# EEZ_DIB_DCM220_r1B2.net
KiCad netlist of a schematic drawn in EAGLE
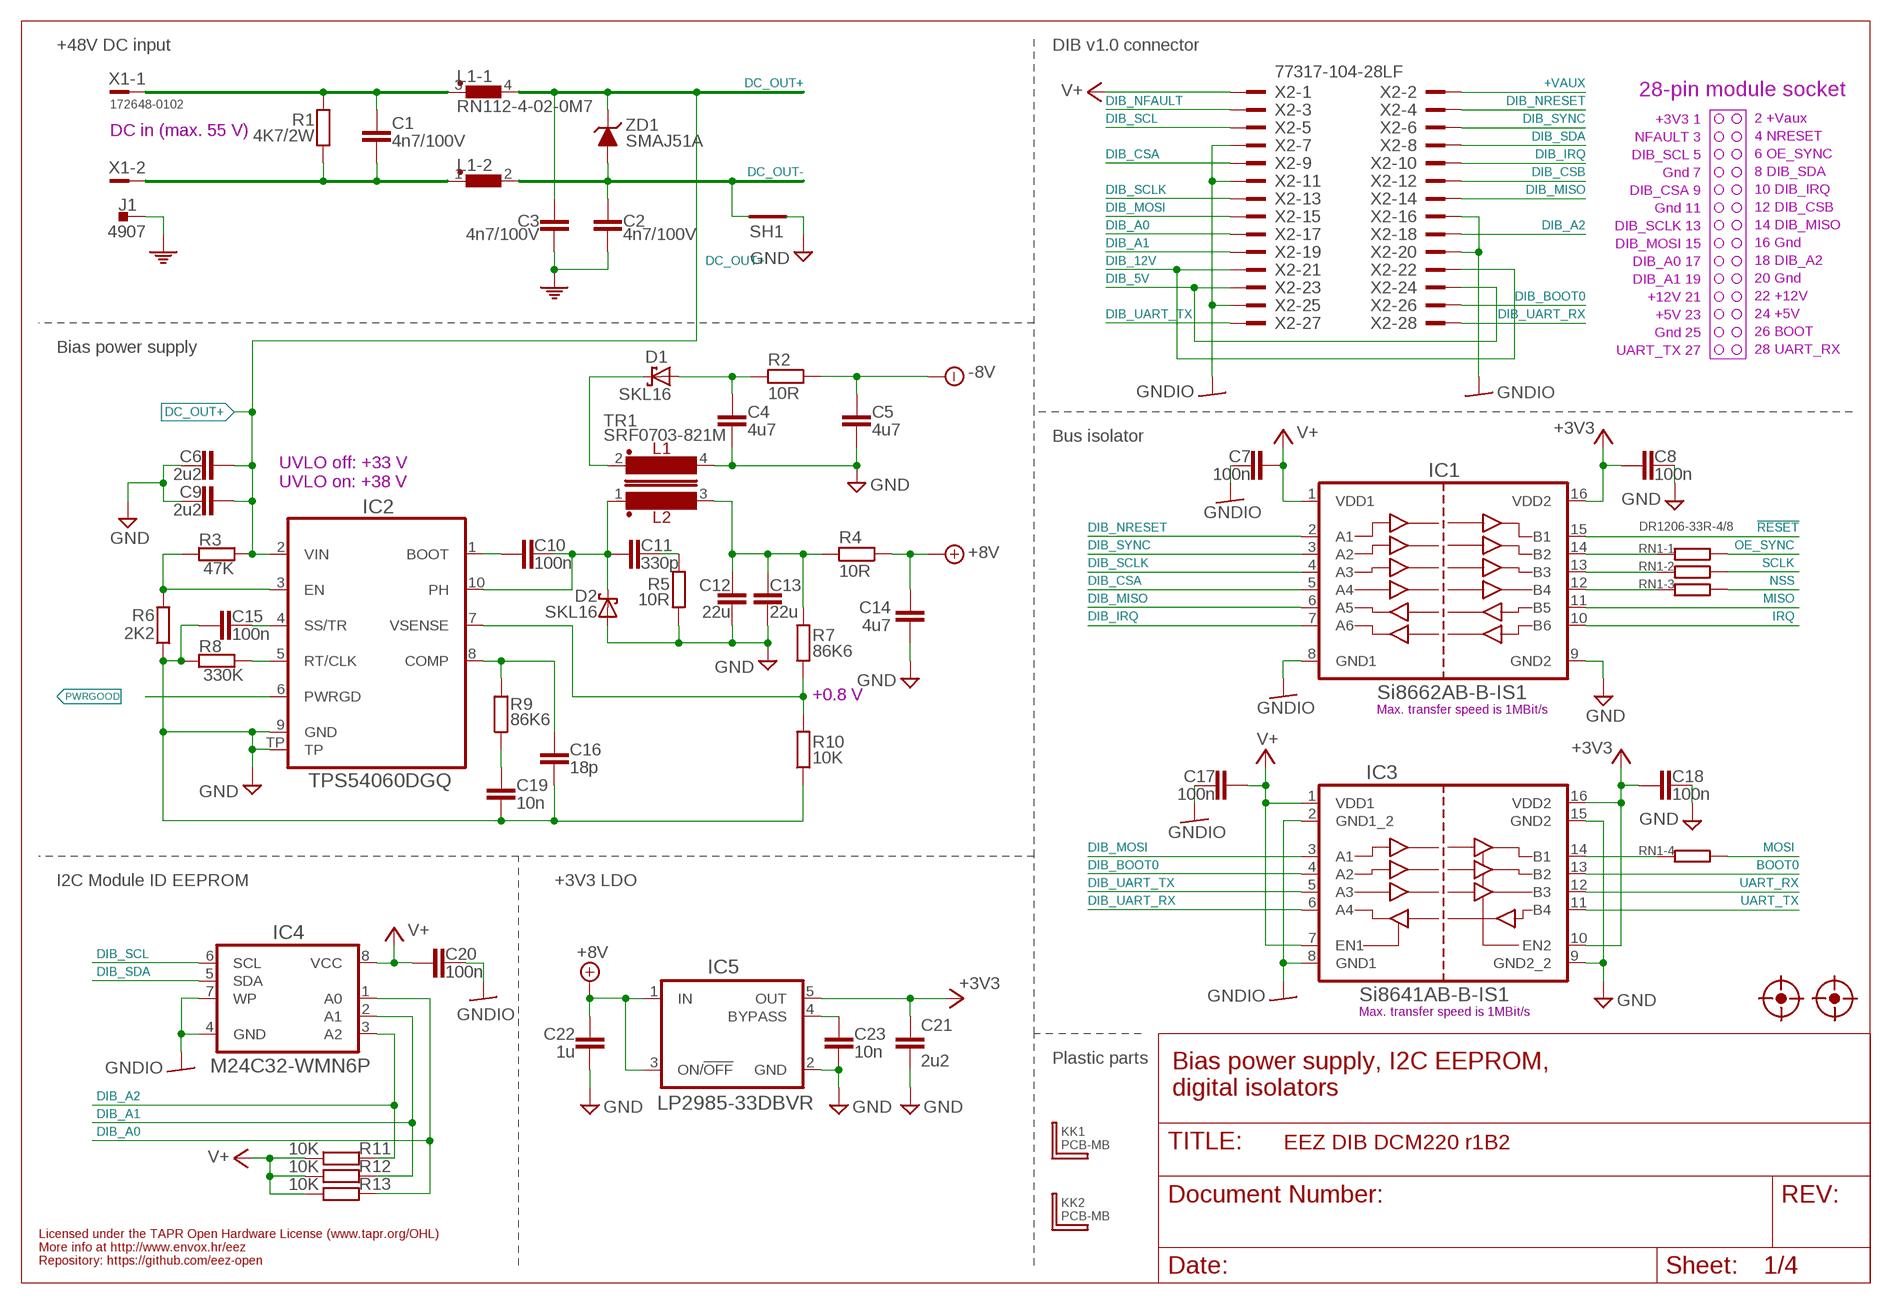
[diagram p0: schematic, sheet 1]
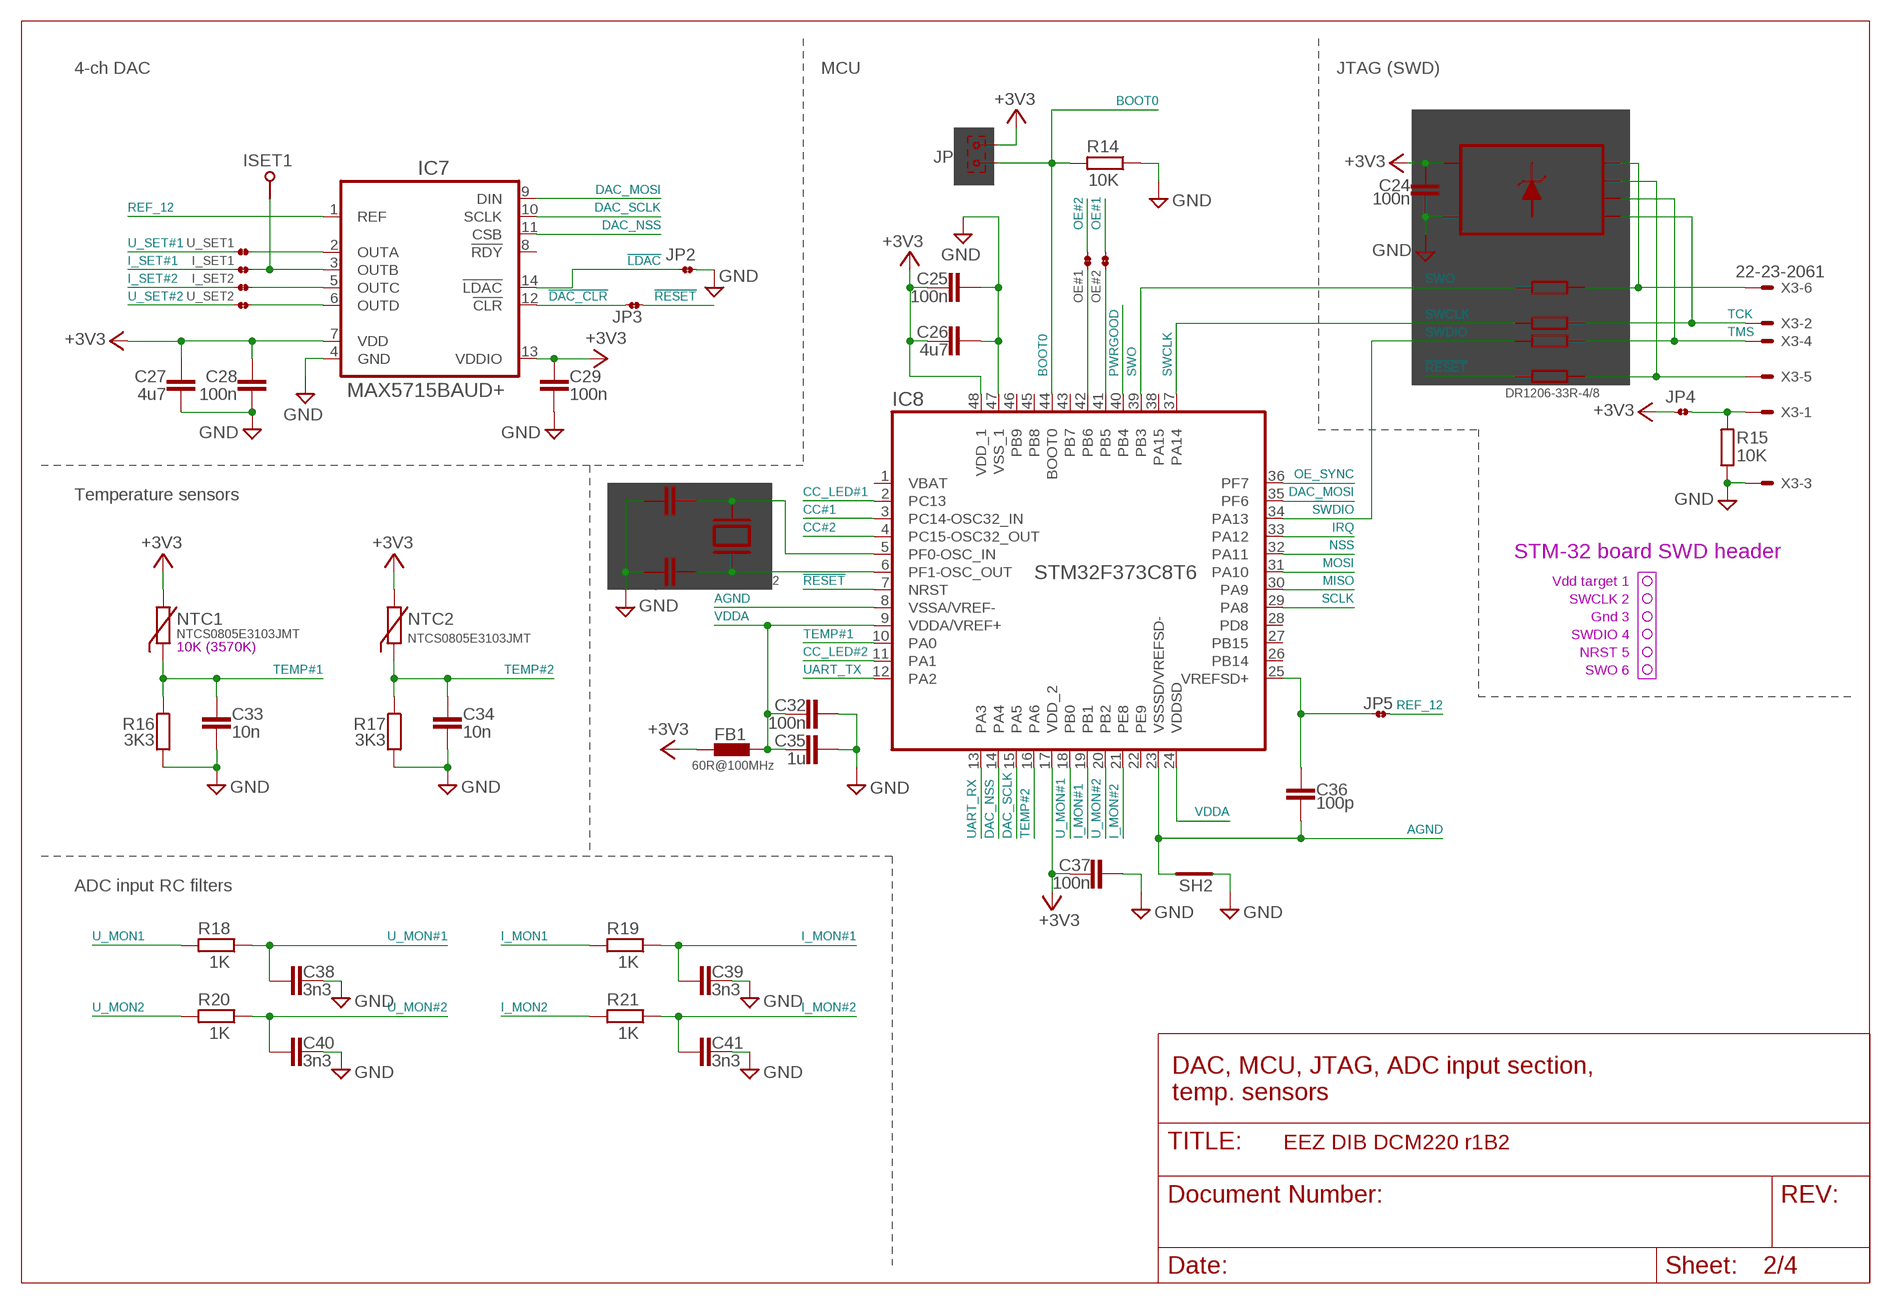
[diagram p1: schematic, sheet 2]
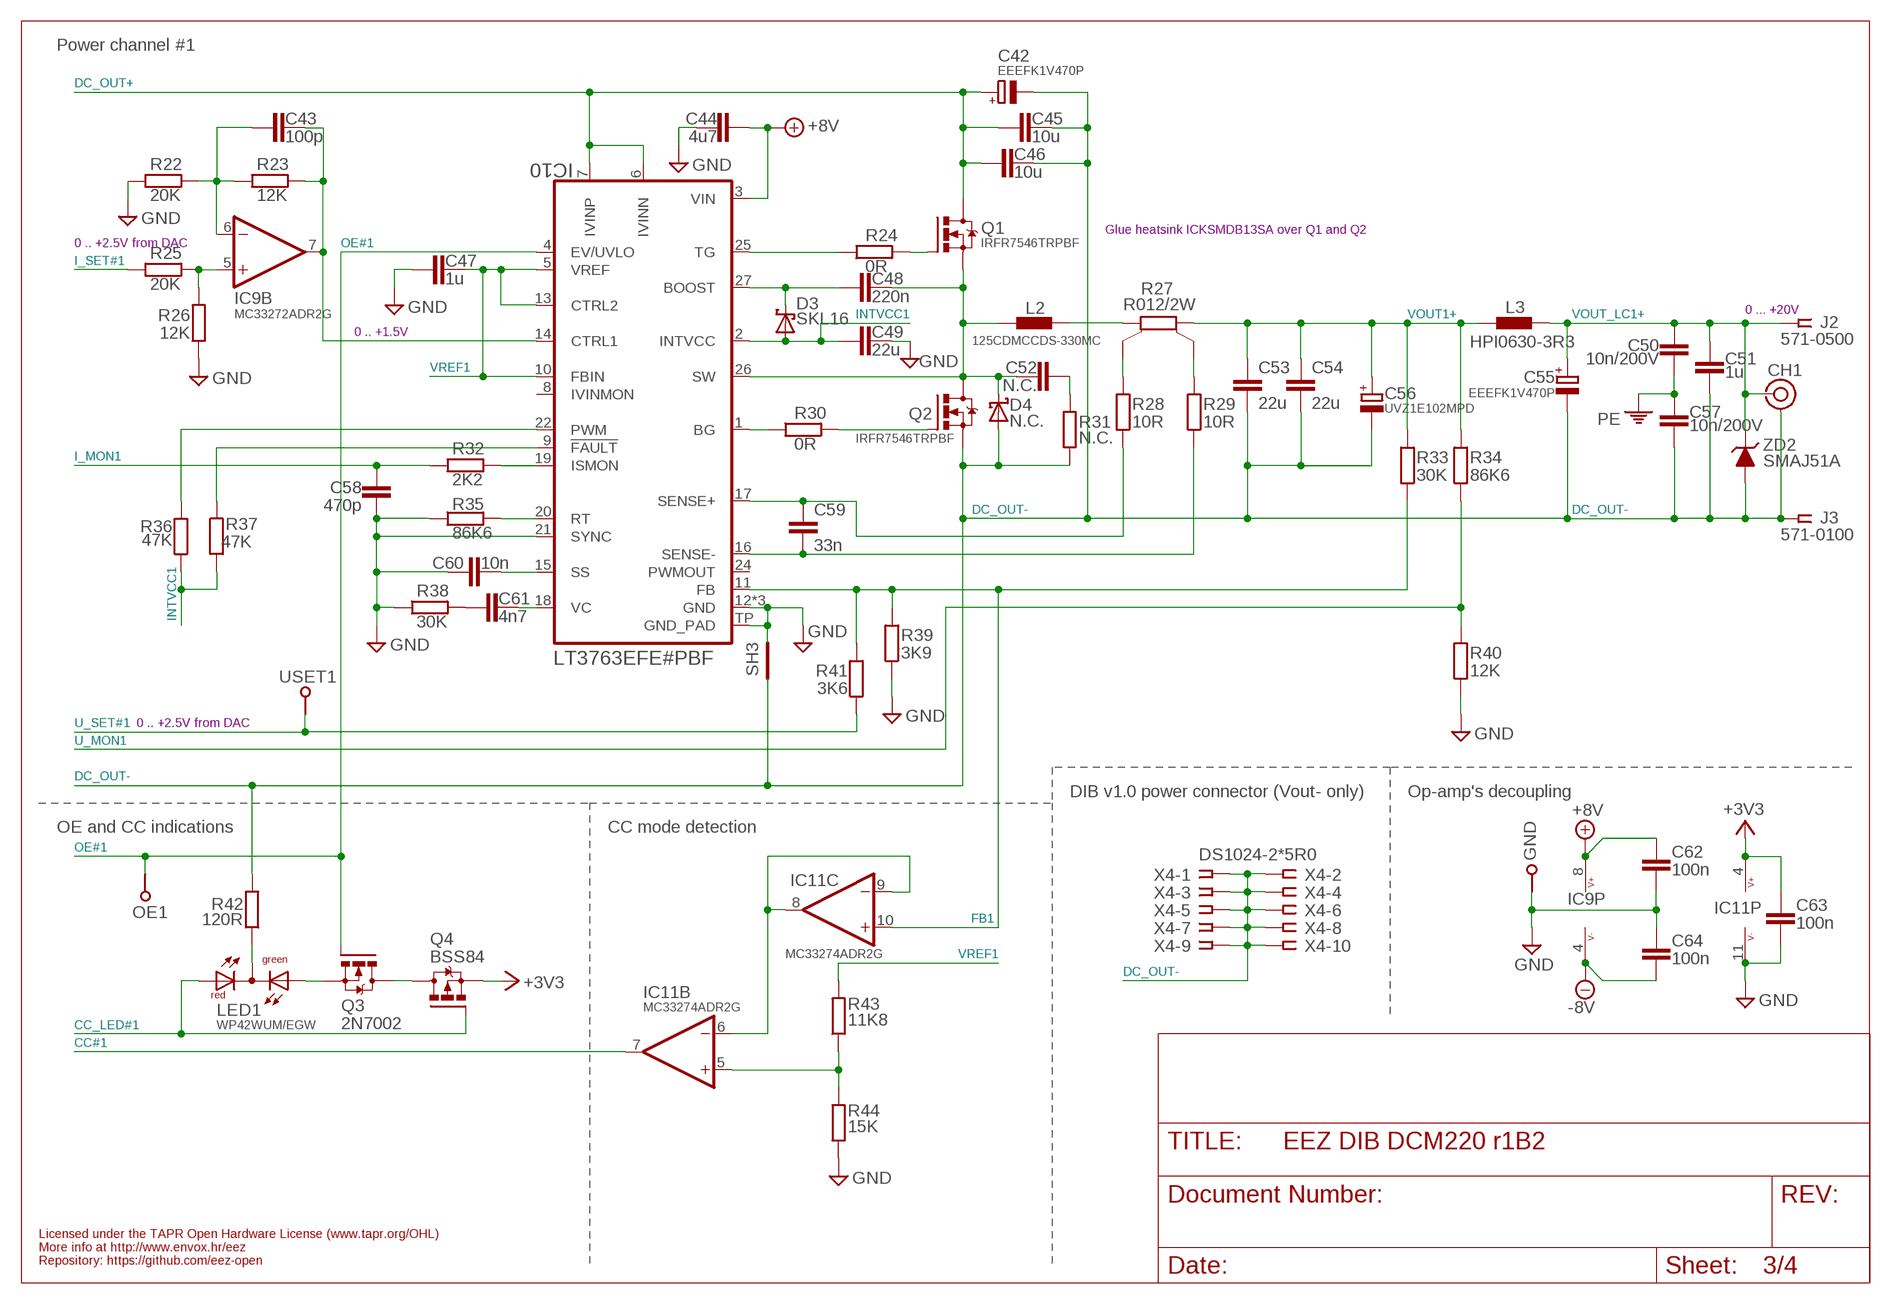
[diagram p2: schematic, sheet 3]
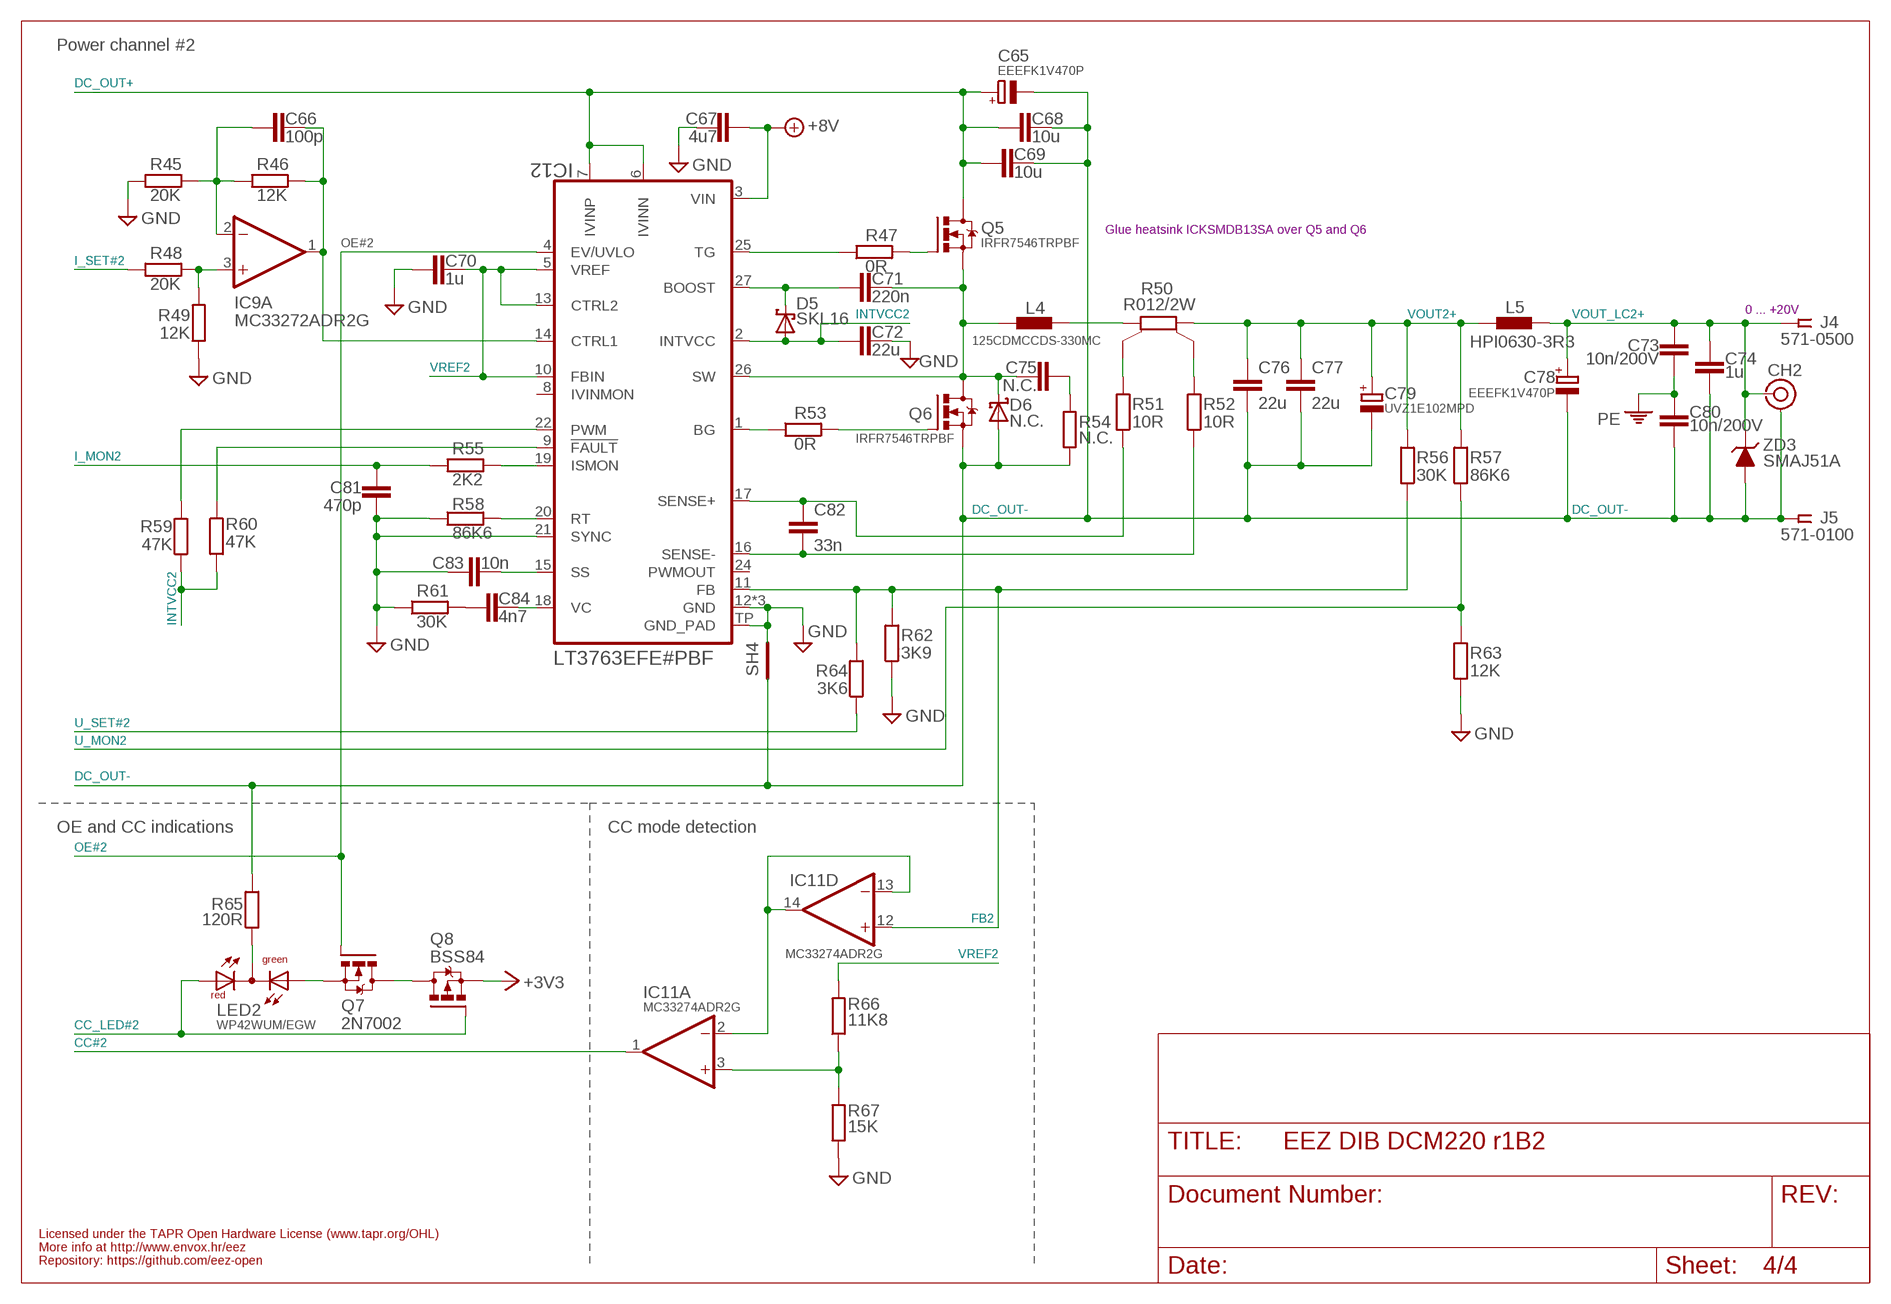
[diagram p3: schematic, sheet 4]

(export (version "E")
  (design (tool "Eeschema 10.0.6"))
  (components
    (comp (ref "C42")
      (value "EEEFK1V470P")
      (footprint "eagle-import:CAPAE830X1050N")
      (libsource (lib "eagle-import") (part "ECAPSMD8.3MM/HA0"))
    )
    (comp (ref "C43")
      (value "100p")
      (footprint "eagle-import:C0805")
      (libsource (lib "eagle-import") (part "C-EUC0805"))
    )
    (comp (ref "C44")
      (value "4u7")
      (footprint "eagle-import:C1206")
      (libsource (lib "eagle-import") (part "C-EUC1206"))
    )
    (comp (ref "C45")
      (value "10u")
      (footprint "eagle-import:C1210")
      (libsource (lib "eagle-import") (part "C-EUC1210"))
    )
    (comp (ref "C46")
      (value "10u")
      (footprint "eagle-import:C1210")
      (libsource (lib "eagle-import") (part "C-EUC1210"))
    )
    (comp (ref "C47")
      (value "1u")
      (footprint "eagle-import:C0805")
      (libsource (lib "eagle-import") (part "C-EUC0805"))
    )
    (comp (ref "C48")
      (value "220n")
      (footprint "eagle-import:C0805")
      (libsource (lib "eagle-import") (part "C-EUC0805"))
    )
    (comp (ref "C49")
      (value "22u")
      (footprint "eagle-import:C1210")
      (libsource (lib "eagle-import") (part "C-EUC1210"))
    )
    (comp (ref "C50")
      (value "10n/200V")
      (footprint "eagle-import:C1206")
      (libsource (lib "eagle-import") (part "C-EUC1206"))
    )
    (comp (ref "C51")
      (value "1u")
      (footprint "eagle-import:C0805")
      (libsource (lib "eagle-import") (part "C-EUC0805"))
    )
    (comp (ref "C52")
      (value "N.C.")
      (footprint "eagle-import:C0805")
      (libsource (lib "eagle-import") (part "C-EUC0805"))
    )
    (comp (ref "C53")
      (value "22u")
      (footprint "eagle-import:C1210")
      (libsource (lib "eagle-import") (part "C-EUC1210"))
    )
    (comp (ref "C54")
      (value "22u")
      (footprint "eagle-import:C1210")
      (libsource (lib "eagle-import") (part "C-EUC1210"))
    )
    (comp (ref "C55")
      (value "EEEFK1V470P")
      (footprint "eagle-import:CAPAE830X1050N")
      (libsource (lib "eagle-import") (part "ECAPSMD8.3MM/HA0"))
    )
    (comp (ref "C56")
      (value "UVZ1E102MPD")
      (footprint "eagle-import:ECAP5_10.5")
      (libsource (lib "eagle-import") (part "ECAP5G_10.5MM"))
    )
    (comp (ref "C57")
      (value "10n/200V")
      (footprint "eagle-import:C1206")
      (libsource (lib "eagle-import") (part "C-EUC1206"))
    )
    (comp (ref "C58")
      (value "470p")
      (footprint "eagle-import:C0805")
      (libsource (lib "eagle-import") (part "C-EUC0805"))
    )
    (comp (ref "C59")
      (value "33n")
      (footprint "eagle-import:C0805")
      (libsource (lib "eagle-import") (part "C-EUC0805"))
    )
    (comp (ref "C60")
      (value "10n")
      (footprint "eagle-import:C0805")
      (libsource (lib "eagle-import") (part "C-EUC0805"))
    )
    (comp (ref "C61")
      (value "4n7")
      (footprint "eagle-import:C0805")
      (libsource (lib "eagle-import") (part "C-EUC0805"))
    )
    (comp (ref "C62")
      (value "100n")
      (footprint "eagle-import:C0603")
      (libsource (lib "eagle-import") (part "C-EUC0603"))
    )
    (comp (ref "C63")
      (value "100n")
      (footprint "eagle-import:C0603")
      (libsource (lib "eagle-import") (part "C-EUC0603"))
    )
    (comp (ref "C64")
      (value "100n")
      (footprint "eagle-import:C0603")
      (libsource (lib "eagle-import") (part "C-EUC0603"))
    )
    (comp (ref "CH1")
      (value "TEST_POINT-2")
      (footprint "eagle-import:TP_1.1MM_2")
      (libsource (lib "eagle-import") (part "TEST_POINT-2"))
    )
    (comp (ref "D3")
      (value "SKL16")
      (footprint "eagle-import:SOD123")
      (libsource (lib "eagle-import") (part "SCHOTTKYSOD123"))
    )
    (comp (ref "D4")
      (value "N.C.")
      (footprint "eagle-import:SMA")
      (libsource (lib "eagle-import") (part "SCHOTTKYSMA_DO-214AC"))
    )
    (comp (ref "GND")
      (value "TEST-PIN_0.9MM")
      (footprint "eagle-import:TEST-PIN_0.9MM")
      (libsource (lib "eagle-import") (part "TEST-PIN_0.9MM"))
    )
    (comp (ref "IC9")
      (value "MC33272ADR2G")
      (footprint "eagle-import:SOIC127P600X173-8N")
      (libsource (lib "eagle-import") (part "TL072SOIC8"))
    )
    (comp (ref "IC10")
      (value "LT3763EFE#PBF")
      (footprint "eagle-import:LTC_05-08-1663-EB")
      (libsource (lib "eagle-import") (part "LT3763EFE#PBF"))
    )
    (comp (ref "IC11")
      (value "MC33274ADR2G")
      (footprint "eagle-import:SOIC127P600X175-14N")
      (fields (field (name "MPN") "TL074ACD"))
      (libsource (lib "eagle-import") (part "TL074SOIC14"))
    )
    (comp (ref "J2")
      (value "571-0500")
      (footprint "eagle-import:DELTRON_571")
      (libsource (lib "eagle-import") (part "571-0500"))
    )
    (comp (ref "J3")
      (value "571-0100")
      (footprint "eagle-import:DELTRON_571")
      (libsource (lib "eagle-import") (part "571-0100"))
    )
    (comp (ref "L2")
      (value "125CDMCCDS-330MC")
      (footprint "eagle-import:125CDMCC_DS")
      (libsource (lib "eagle-import") (part "125CDMCC/DS"))
    )
    (comp (ref "L3")
      (value "HPI0630-3R3")
      (footprint "eagle-import:COILCRAFT_HPI0630")
      (libsource (lib "eagle-import") (part "COILCRAFT_HPI0630"))
    )
    (comp (ref "LED1")
      (value "WP42WUM/EGW")
      (footprint "eagle-import:L-42WUM-1EGWT")
      (libsource (lib "eagle-import") (part "LED_L-42WUM/1EGWT"))
    )
    (comp (ref "OE1")
      (value "TEST-PIN_0.9MM")
      (footprint "eagle-import:TEST-PIN_0.9MM")
      (libsource (lib "eagle-import") (part "TEST-PIN_0.9MM"))
    )
    (comp (ref "Q1")
      (value "IRFR7546TRPBF")
      (footprint "eagle-import:TO229P990X239-3N")
      (libsource (lib "eagle-import") (part "N-MOSFETDPAK"))
    )
    (comp (ref "Q2")
      (value "IRFR7546TRPBF")
      (footprint "eagle-import:TO229P990X239-3N")
      (libsource (lib "eagle-import") (part "N-MOSFETDPAK"))
    )
    (comp (ref "Q3")
      (value "2N7002")
      (footprint "eagle-import:SOT103P240X110-3N")
      (fields (field (name "MPN") "2N7002-7-F"))
      (libsource (lib "eagle-import") (part "2N7002"))
    )
    (comp (ref "Q4")
      (value "BSS84")
      (footprint "eagle-import:SOT95P237X112-3N")
      (fields (field (name "MPN") "IRLML2246TRPBF"))
      (libsource (lib "eagle-import") (part "IRLML2246TRPBF"))
    )
    (comp (ref "R22")
      (value "20K")
      (footprint "eagle-import:R0805")
      (libsource (lib "eagle-import") (part "R-EU_R0805"))
    )
    (comp (ref "R23")
      (value "12K")
      (footprint "eagle-import:R0805")
      (libsource (lib "eagle-import") (part "R-EU_R0805"))
    )
    (comp (ref "R24")
      (value "0R")
      (footprint "eagle-import:R0805")
      (libsource (lib "eagle-import") (part "R-EU_R0805"))
    )
    (comp (ref "R25")
      (value "20K")
      (footprint "eagle-import:R0805")
      (libsource (lib "eagle-import") (part "R-EU_R0805"))
    )
    (comp (ref "R26")
      (value "12K")
      (footprint "eagle-import:R0805")
      (libsource (lib "eagle-import") (part "R-EU_R0805"))
    )
    (comp (ref "R27")
      (value "R012/2W")
      (footprint "eagle-import:R_2512-4WIRE")
      (libsource (lib "eagle-import") (part "R-EU_4WIRE2512"))
    )
    (comp (ref "R28")
      (value "10R")
      (footprint "eagle-import:R0805")
      (libsource (lib "eagle-import") (part "R-EU_R0805"))
    )
    (comp (ref "R29")
      (value "10R")
      (footprint "eagle-import:R0805")
      (libsource (lib "eagle-import") (part "R-EU_R0805"))
    )
    (comp (ref "R30")
      (value "0R")
      (footprint "eagle-import:R0805")
      (libsource (lib "eagle-import") (part "R-EU_R0805"))
    )
    (comp (ref "R31")
      (value "N.C.")
      (footprint "eagle-import:R1206")
      (libsource (lib "eagle-import") (part "R-EU_R1206"))
    )
    (comp (ref "R32")
      (value "2K2")
      (footprint "eagle-import:R0805")
      (libsource (lib "eagle-import") (part "R-EU_R0805"))
    )
    (comp (ref "R33")
      (value "30K")
      (footprint "eagle-import:R0805")
      (libsource (lib "eagle-import") (part "R-EU_R0805"))
    )
    (comp (ref "R34")
      (value "86K6")
      (footprint "eagle-import:R0805")
      (libsource (lib "eagle-import") (part "R-EU_R0805"))
    )
    (comp (ref "R35")
      (value "86K6")
      (footprint "eagle-import:R0805")
      (libsource (lib "eagle-import") (part "R-EU_R0805"))
    )
    (comp (ref "R36")
      (value "47K")
      (footprint "eagle-import:R0805")
      (libsource (lib "eagle-import") (part "R-EU_R0805"))
    )
    (comp (ref "R37")
      (value "47K")
      (footprint "eagle-import:R0805")
      (libsource (lib "eagle-import") (part "R-EU_R0805"))
    )
    (comp (ref "R38")
      (value "30K")
      (footprint "eagle-import:R0805")
      (libsource (lib "eagle-import") (part "R-EU_R0805"))
    )
    (comp (ref "R39")
      (value "3K9")
      (footprint "eagle-import:R0805")
      (libsource (lib "eagle-import") (part "R-EU_R0805"))
    )
    (comp (ref "R40")
      (value "12K")
      (footprint "eagle-import:R0805")
      (libsource (lib "eagle-import") (part "R-EU_R0805"))
    )
    (comp (ref "R41")
      (value "3K6")
      (footprint "eagle-import:R0805")
      (libsource (lib "eagle-import") (part "R-EU_R0805"))
    )
    (comp (ref "R42")
      (value "120R")
      (footprint "eagle-import:R0805")
      (libsource (lib "eagle-import") (part "R-EU_R0805"))
    )
    (comp (ref "R43")
      (value "11K8")
      (footprint "eagle-import:R0805")
      (libsource (lib "eagle-import") (part "R-EU_R0805"))
    )
    (comp (ref "R44")
      (value "15K")
      (footprint "eagle-import:R0805")
      (libsource (lib "eagle-import") (part "R-EU_R0805"))
    )
    (comp (ref "SH3")
      (value "SHORTNOHOLE")
      (footprint "eagle-import:SHORT_NOHOLE")
      (libsource (lib "eagle-import") (part "SHORTNOHOLE"))
    )
    (comp (ref "USET1")
      (value "TEST-PIN_0.9MM")
      (footprint "eagle-import:TEST-PIN_0.9MM")
      (libsource (lib "eagle-import") (part "TEST-PIN_0.9MM"))
    )
    (comp (ref "X4")
      (value "DS1024-2*5R0")
      (footprint "eagle-import:SSW-105-02-T-D-RA")
      (libsource (lib "eagle-import") (part "SSW-105-02-T-D-RA"))
    )
    (comp (ref "ZD2")
      (value "SMAJ51A")
      (footprint "eagle-import:DO214AA")
      (libsource (lib "eagle-import") (part "P6SMB68A"))
    )
    (comp (ref "C1")
      (value "4n7/100V")
      (footprint "eagle-import:C1206")
      (libsource (lib "eagle-import") (part "C-EUC1206"))
    )
    (comp (ref "C2")
      (value "4n7/100V")
      (footprint "eagle-import:C1206")
      (libsource (lib "eagle-import") (part "C-EUC1206"))
    )
    (comp (ref "C3")
      (value "4n7/100V")
      (footprint "eagle-import:C1206")
      (libsource (lib "eagle-import") (part "C-EUC1206"))
    )
    (comp (ref "C4")
      (value "4u7")
      (footprint "eagle-import:C1206")
      (libsource (lib "eagle-import") (part "C-EUC1206"))
    )
    (comp (ref "C5")
      (value "4u7")
      (footprint "eagle-import:C1206")
      (libsource (lib "eagle-import") (part "C-EUC1206"))
    )
    (comp (ref "C6")
      (value "2u2")
      (footprint "eagle-import:C1206")
      (libsource (lib "eagle-import") (part "C-EUC1206"))
    )
    (comp (ref "C7")
      (value "100n")
      (footprint "eagle-import:C0603")
      (libsource (lib "eagle-import") (part "C-EUC0603"))
    )
    (comp (ref "C8")
      (value "100n")
      (footprint "eagle-import:C0603")
      (libsource (lib "eagle-import") (part "C-EUC0603"))
    )
    (comp (ref "C9")
      (value "2u2")
      (footprint "eagle-import:C1206")
      (libsource (lib "eagle-import") (part "C-EUC1206"))
    )
    (comp (ref "C10")
      (value "100n")
      (footprint "eagle-import:C0603")
      (libsource (lib "eagle-import") (part "C-EUC0603"))
    )
    (comp (ref "C11")
      (value "330p")
      (footprint "eagle-import:C0805")
      (libsource (lib "eagle-import") (part "C-EUC0805"))
    )
    (comp (ref "C12")
      (value "22u")
      (footprint "eagle-import:C1206")
      (libsource (lib "eagle-import") (part "C-EUC1206"))
    )
    (comp (ref "C13")
      (value "22u")
      (footprint "eagle-import:C1206")
      (libsource (lib "eagle-import") (part "C-EUC1206"))
    )
    (comp (ref "C14")
      (value "4u7")
      (footprint "eagle-import:C1206")
      (libsource (lib "eagle-import") (part "C-EUC1206"))
    )
    (comp (ref "C15")
      (value "100n")
      (footprint "eagle-import:C0603")
      (libsource (lib "eagle-import") (part "C-EUC0603"))
    )
    (comp (ref "C16")
      (value "18p")
      (footprint "eagle-import:C0603")
      (libsource (lib "eagle-import") (part "C-EUC0603"))
    )
    (comp (ref "C17")
      (value "100n")
      (footprint "eagle-import:C0603")
      (libsource (lib "eagle-import") (part "C-EUC0603"))
    )
    (comp (ref "C18")
      (value "100n")
      (footprint "eagle-import:C0603")
      (libsource (lib "eagle-import") (part "C-EUC0603"))
    )
    (comp (ref "C19")
      (value "10n")
      (footprint "eagle-import:C0805")
      (libsource (lib "eagle-import") (part "C-EUC0805"))
    )
    (comp (ref "C20")
      (value "100n")
      (footprint "eagle-import:C0603")
      (libsource (lib "eagle-import") (part "C-EUC0603"))
    )
    (comp (ref "C21")
      (value "2u2")
      (footprint "eagle-import:C1206")
      (libsource (lib "eagle-import") (part "C-EUC1206"))
    )
    (comp (ref "C22")
      (value "1u")
      (footprint "eagle-import:C0805")
      (libsource (lib "eagle-import") (part "C-EUC0805"))
    )
    (comp (ref "C23")
      (value "10n")
      (footprint "eagle-import:C0805")
      (libsource (lib "eagle-import") (part "C-EUC0805"))
    )
    (comp (ref "D1")
      (value "SKL16")
      (footprint "eagle-import:SOD123")
      (libsource (lib "eagle-import") (part "SCHOTTKYSOD123"))
    )
    (comp (ref "D2")
      (value "SKL16")
      (footprint "eagle-import:SOD123")
      (libsource (lib "eagle-import") (part "SCHOTTKYSOD123"))
    )
    (comp (ref "FM1")
      (value "FIDUCIAL_2")
      (footprint "eagle-import:FIDUCIAL_DUAL")
      (libsource (lib "eagle-import") (part "FIDUCIAL_2"))
    )
    (comp (ref "FM2")
      (value "FIDUCIAL_2")
      (footprint "eagle-import:FIDUCIAL_DUAL")
      (libsource (lib "eagle-import") (part "FIDUCIAL_2"))
    )
    (comp (ref "IC1")
      (value "Si8662AB-B-IS1")
      (footprint "eagle-import:SOIC-16")
      (libsource (lib "eagle-import") (part "SI8662NSOIC-16"))
    )
    (comp (ref "IC2")
      (value "TPS54060DGQ")
      (footprint "eagle-import:SOP50P490X110-11N")
      (fields (field (name "MPN") "TPS54060ADGQ"))
      (libsource (lib "eagle-import") (part "TPS54060DGQ"))
    )
    (comp (ref "IC3")
      (value "Si8641AB-B-IS1")
      (footprint "eagle-import:SOIC-16")
      (libsource (lib "eagle-import") (part "SI8641NSOIC-16"))
    )
    (comp (ref "IC4")
      (value "M24C32-WMN6P")
      (footprint "eagle-import:SOIC127P600X173-8N")
      (libsource (lib "eagle-import") (part "AT24CXXSOIC8"))
    )
    (comp (ref "IC5")
      (value "LP2985-33DBVR")
      (footprint "eagle-import:SOT95P270X145-5N")
      (libsource (lib "eagle-import") (part "LP2985"))
    )
    (comp (ref "J1")
      (value "4907")
      (footprint "eagle-import:PCB_TAB-4907")
      (libsource (lib "eagle-import") (part "PCB_TAB-4907"))
    )
    (comp (ref "KK1")
      (value "PCB-MB")
      (footprint "eagle-import:PCB-MB")
      (libsource (lib "eagle-import") (part "PCB-MB"))
    )
    (comp (ref "KK2")
      (value "PCB-MB")
      (footprint "eagle-import:PCB-MB")
      (libsource (lib "eagle-import") (part "PCB-MB"))
    )
    (comp (ref "L1")
      (value "RN112-4-02-0M7")
      (footprint "eagle-import:RN112")
      (libsource (lib "eagle-import") (part "RN112"))
    )
    (comp (ref "R1")
      (value "4K7/2W")
      (footprint "eagle-import:R2512")
      (libsource (lib "eagle-import") (part "R-EU_R2512"))
    )
    (comp (ref "R2")
      (value "10R")
      (footprint "eagle-import:R0805")
      (libsource (lib "eagle-import") (part "R-EU_R0805"))
    )
    (comp (ref "R3")
      (value "47K")
      (footprint "eagle-import:R0805")
      (libsource (lib "eagle-import") (part "R-EU_R0805"))
    )
    (comp (ref "R4")
      (value "10R")
      (footprint "eagle-import:R0805")
      (libsource (lib "eagle-import") (part "R-EU_R0805"))
    )
    (comp (ref "R5")
      (value "10R")
      (footprint "eagle-import:R0805")
      (libsource (lib "eagle-import") (part "R-EU_R0805"))
    )
    (comp (ref "R6")
      (value "2K2")
      (footprint "eagle-import:R0805")
      (libsource (lib "eagle-import") (part "R-EU_R0805"))
    )
    (comp (ref "R7")
      (value "86K6")
      (footprint "eagle-import:R0805")
      (libsource (lib "eagle-import") (part "R-EU_R0805"))
    )
    (comp (ref "R8")
      (value "330K")
      (footprint "eagle-import:R0805")
      (libsource (lib "eagle-import") (part "R-EU_R0805"))
    )
    (comp (ref "R9")
      (value "86K6")
      (footprint "eagle-import:R0805")
      (libsource (lib "eagle-import") (part "R-EU_R0805"))
    )
    (comp (ref "R10")
      (value "10K")
      (footprint "eagle-import:R0805")
      (libsource (lib "eagle-import") (part "R-EU_R0805"))
    )
    (comp (ref "R11")
      (value "10K")
      (footprint "eagle-import:R0805")
      (libsource (lib "eagle-import") (part "R-EU_R0805"))
    )
    (comp (ref "R12")
      (value "10K")
      (footprint "eagle-import:R0805")
      (libsource (lib "eagle-import") (part "R-EU_R0805"))
    )
    (comp (ref "R13")
      (value "10K")
      (footprint "eagle-import:R0805")
      (libsource (lib "eagle-import") (part "R-EU_R0805"))
    )
    (comp (ref "RN1")
      (value "DR1206-33R-4/8")
      (footprint "eagle-import:CAY16")
      (libsource (lib "eagle-import") (part "R_ARRAY4"))
    )
    (comp (ref "SH1")
      (value "SHORTNOHOLE")
      (footprint "eagle-import:SHORT_NOHOLE")
      (libsource (lib "eagle-import") (part "SHORTNOHOLE"))
    )
    (comp (ref "TR1")
      (value "SRF0703-821M")
      (footprint "eagle-import:SRF0703")
      (libsource (lib "eagle-import") (part "BOURNS_SRF0703INV"))
    )
    (comp (ref "X1")
      (value "172648-0102")
      (footprint "eagle-import:MINIFIT_39301020")
      (libsource (lib "eagle-import") (part "MINIFIT_39301020"))
    )
    (comp (ref "X2")
      (value "77317-104-28LF")
      (footprint "eagle-import:77317-104-28LF")
      (libsource (lib "eagle-import") (part "77317-104-28LF"))
    )
    (comp (ref "ZD1")
      (value "SMAJ51A")
      (footprint "eagle-import:DO214AA")
      (libsource (lib "eagle-import") (part "P6SMB68A"))
    )
    (comp (ref "C65")
      (value "EEEFK1V470P")
      (footprint "eagle-import:CAPAE830X1050N")
      (libsource (lib "eagle-import") (part "ECAPSMD8.3MM/HA0"))
    )
    (comp (ref "C66")
      (value "100p")
      (footprint "eagle-import:C0805")
      (libsource (lib "eagle-import") (part "C-EUC0805"))
    )
    (comp (ref "C67")
      (value "4u7")
      (footprint "eagle-import:C1206")
      (libsource (lib "eagle-import") (part "C-EUC1206"))
    )
    (comp (ref "C68")
      (value "10u")
      (footprint "eagle-import:C1210")
      (libsource (lib "eagle-import") (part "C-EUC1210"))
    )
    (comp (ref "C69")
      (value "10u")
      (footprint "eagle-import:C1210")
      (libsource (lib "eagle-import") (part "C-EUC1210"))
    )
    (comp (ref "C70")
      (value "1u")
      (footprint "eagle-import:C0805")
      (libsource (lib "eagle-import") (part "C-EUC0805"))
    )
    (comp (ref "C71")
      (value "220n")
      (footprint "eagle-import:C0805")
      (libsource (lib "eagle-import") (part "C-EUC0805"))
    )
    (comp (ref "C72")
      (value "22u")
      (footprint "eagle-import:C1210")
      (libsource (lib "eagle-import") (part "C-EUC1210"))
    )
    (comp (ref "C73")
      (value "10n/200V")
      (footprint "eagle-import:C1206")
      (libsource (lib "eagle-import") (part "C-EUC1206"))
    )
    (comp (ref "C74")
      (value "1u")
      (footprint "eagle-import:C0805")
      (libsource (lib "eagle-import") (part "C-EUC0805"))
    )
    (comp (ref "C75")
      (value "N.C.")
      (footprint "eagle-import:C0805")
      (libsource (lib "eagle-import") (part "C-EUC0805"))
    )
    (comp (ref "C76")
      (value "22u")
      (footprint "eagle-import:C1210")
      (libsource (lib "eagle-import") (part "C-EUC1210"))
    )
    (comp (ref "C77")
      (value "22u")
      (footprint "eagle-import:C1210")
      (libsource (lib "eagle-import") (part "C-EUC1210"))
    )
    (comp (ref "C78")
      (value "EEEFK1V470P")
      (footprint "eagle-import:CAPAE830X1050N")
      (libsource (lib "eagle-import") (part "ECAPSMD8.3MM/HA0"))
    )
    (comp (ref "C79")
      (value "UVZ1E102MPD")
      (footprint "eagle-import:ECAP5_10.5")
      (libsource (lib "eagle-import") (part "ECAP5G_10.5MM"))
    )
    (comp (ref "C80")
      (value "10n/200V")
      (footprint "eagle-import:C1206")
      (libsource (lib "eagle-import") (part "C-EUC1206"))
    )
    (comp (ref "C81")
      (value "470p")
      (footprint "eagle-import:C0805")
      (libsource (lib "eagle-import") (part "C-EUC0805"))
    )
    (comp (ref "C82")
      (value "33n")
      (footprint "eagle-import:C0805")
      (libsource (lib "eagle-import") (part "C-EUC0805"))
    )
    (comp (ref "C83")
      (value "10n")
      (footprint "eagle-import:C0805")
      (libsource (lib "eagle-import") (part "C-EUC0805"))
    )
    (comp (ref "C84")
      (value "4n7")
      (footprint "eagle-import:C0805")
      (libsource (lib "eagle-import") (part "C-EUC0805"))
    )
    (comp (ref "CH2")
      (value "TEST_POINT-2")
      (footprint "eagle-import:TP_1.1MM_2")
      (libsource (lib "eagle-import") (part "TEST_POINT-2"))
    )
    (comp (ref "D5")
      (value "SKL16")
      (footprint "eagle-import:SOD123")
      (libsource (lib "eagle-import") (part "SCHOTTKYSOD123"))
    )
    (comp (ref "D6")
      (value "N.C.")
      (footprint "eagle-import:SMA")
      (libsource (lib "eagle-import") (part "SCHOTTKYSMA_DO-214AC"))
    )
    (comp (ref "IC12")
      (value "LT3763EFE#PBF")
      (footprint "eagle-import:LTC_05-08-1663-EB")
      (libsource (lib "eagle-import") (part "LT3763EFE#PBF"))
    )
    (comp (ref "J4")
      (value "571-0500")
      (footprint "eagle-import:DELTRON_571")
      (libsource (lib "eagle-import") (part "571-0500"))
    )
    (comp (ref "J5")
      (value "571-0100")
      (footprint "eagle-import:DELTRON_571")
      (libsource (lib "eagle-import") (part "571-0100"))
    )
    (comp (ref "L4")
      (value "125CDMCCDS-330MC")
      (footprint "eagle-import:125CDMCC_DS")
      (libsource (lib "eagle-import") (part "125CDMCC/DS"))
    )
    (comp (ref "L5")
      (value "HPI0630-3R3")
      (footprint "eagle-import:COILCRAFT_HPI0630")
      (libsource (lib "eagle-import") (part "COILCRAFT_HPI0630"))
    )
    (comp (ref "LED2")
      (value "WP42WUM/EGW")
      (footprint "eagle-import:L-42WUM-1EGWT")
      (libsource (lib "eagle-import") (part "LED_L-42WUM/1EGWT"))
    )
    (comp (ref "Q5")
      (value "IRFR7546TRPBF")
      (footprint "eagle-import:TO229P990X239-3N")
      (libsource (lib "eagle-import") (part "N-MOSFETDPAK"))
    )
    (comp (ref "Q6")
      (value "IRFR7546TRPBF")
      (footprint "eagle-import:TO229P990X239-3N")
      (libsource (lib "eagle-import") (part "N-MOSFETDPAK"))
    )
    (comp (ref "Q7")
      (value "2N7002")
      (footprint "eagle-import:SOT103P240X110-3N")
      (fields (field (name "MPN") "2N7002-7-F"))
      (libsource (lib "eagle-import") (part "2N7002"))
    )
    (comp (ref "Q8")
      (value "BSS84")
      (footprint "eagle-import:SOT95P237X112-3N")
      (fields (field (name "MPN") "IRLML2246TRPBF"))
      (libsource (lib "eagle-import") (part "IRLML2246TRPBF"))
    )
    (comp (ref "R45")
      (value "20K")
      (footprint "eagle-import:R0805")
      (libsource (lib "eagle-import") (part "R-EU_R0805"))
    )
    (comp (ref "R46")
      (value "12K")
      (footprint "eagle-import:R0805")
      (libsource (lib "eagle-import") (part "R-EU_R0805"))
    )
    (comp (ref "R47")
      (value "0R")
      (footprint "eagle-import:R0805")
      (libsource (lib "eagle-import") (part "R-EU_R0805"))
    )
    (comp (ref "R48")
      (value "20K")
      (footprint "eagle-import:R0805")
      (libsource (lib "eagle-import") (part "R-EU_R0805"))
    )
    (comp (ref "R49")
      (value "12K")
      (footprint "eagle-import:R0805")
      (libsource (lib "eagle-import") (part "R-EU_R0805"))
    )
    (comp (ref "R50")
      (value "R012/2W")
      (footprint "eagle-import:R_2512-4WIRE")
      (libsource (lib "eagle-import") (part "R-EU_4WIRE2512"))
    )
    (comp (ref "R51")
      (value "10R")
      (footprint "eagle-import:R0805")
      (libsource (lib "eagle-import") (part "R-EU_R0805"))
    )
    (comp (ref "R52")
      (value "10R")
      (footprint "eagle-import:R0805")
      (libsource (lib "eagle-import") (part "R-EU_R0805"))
    )
    (comp (ref "R53")
      (value "0R")
      (footprint "eagle-import:R0805")
      (libsource (lib "eagle-import") (part "R-EU_R0805"))
    )
    (comp (ref "R54")
      (value "N.C.")
      (footprint "eagle-import:R1206")
      (libsource (lib "eagle-import") (part "R-EU_R1206"))
    )
    (comp (ref "R55")
      (value "2K2")
      (footprint "eagle-import:R0805")
      (libsource (lib "eagle-import") (part "R-EU_R0805"))
    )
    (comp (ref "R56")
      (value "30K")
      (footprint "eagle-import:R0805")
      (libsource (lib "eagle-import") (part "R-EU_R0805"))
    )
    (comp (ref "R57")
      (value "86K6")
      (footprint "eagle-import:R0805")
      (libsource (lib "eagle-import") (part "R-EU_R0805"))
    )
    (comp (ref "R58")
      (value "86K6")
      (footprint "eagle-import:R0805")
      (libsource (lib "eagle-import") (part "R-EU_R0805"))
    )
    (comp (ref "R59")
      (value "47K")
      (footprint "eagle-import:R0805")
      (libsource (lib "eagle-import") (part "R-EU_R0805"))
    )
    (comp (ref "R60")
      (value "47K")
      (footprint "eagle-import:R0805")
      (libsource (lib "eagle-import") (part "R-EU_R0805"))
    )
    (comp (ref "R61")
      (value "30K")
      (footprint "eagle-import:R0805")
      (libsource (lib "eagle-import") (part "R-EU_R0805"))
    )
    (comp (ref "R62")
      (value "3K9")
      (footprint "eagle-import:R0805")
      (libsource (lib "eagle-import") (part "R-EU_R0805"))
    )
    (comp (ref "R63")
      (value "12K")
      (footprint "eagle-import:R0805")
      (libsource (lib "eagle-import") (part "R-EU_R0805"))
    )
    (comp (ref "R64")
      (value "3K6")
      (footprint "eagle-import:R0805")
      (libsource (lib "eagle-import") (part "R-EU_R0805"))
    )
    (comp (ref "R65")
      (value "120R")
      (footprint "eagle-import:R0805")
      (libsource (lib "eagle-import") (part "R-EU_R0805"))
    )
    (comp (ref "R66")
      (value "11K8")
      (footprint "eagle-import:R0805")
      (libsource (lib "eagle-import") (part "R-EU_R0805"))
    )
    (comp (ref "R67")
      (value "15K")
      (footprint "eagle-import:R0805")
      (libsource (lib "eagle-import") (part "R-EU_R0805"))
    )
    (comp (ref "SH4")
      (value "SHORTNOHOLE")
      (footprint "eagle-import:SHORT_NOHOLE")
      (libsource (lib "eagle-import") (part "SHORTNOHOLE"))
    )
    (comp (ref "ZD3")
      (value "SMAJ51A")
      (footprint "eagle-import:DO214AA")
      (libsource (lib "eagle-import") (part "P6SMB68A"))
    )
    (comp (ref "C24")
      (value "100n")
      (footprint "eagle-import:C0603")
      (libsource (lib "eagle-import") (part "C-EUC0603"))
    )
    (comp (ref "C25")
      (value "100n")
      (footprint "eagle-import:C0603")
      (libsource (lib "eagle-import") (part "C-EUC0603"))
    )
    (comp (ref "C26")
      (value "4u7")
      (footprint "eagle-import:C1206")
      (libsource (lib "eagle-import") (part "C-EUC1206"))
    )
    (comp (ref "C27")
      (value "4u7")
      (footprint "eagle-import:C1206")
      (libsource (lib "eagle-import") (part "C-EUC1206"))
    )
    (comp (ref "C28")
      (value "100n")
      (footprint "eagle-import:C0603")
      (libsource (lib "eagle-import") (part "C-EUC0603"))
    )
    (comp (ref "C29")
      (value "100n")
      (footprint "eagle-import:C0603")
      (libsource (lib "eagle-import") (part "C-EUC0603"))
    )
    (comp (ref "C30")
      (value "18p")
      (footprint "eagle-import:C0603")
      (libsource (lib "eagle-import") (part "C-EUC0603"))
    )
    (comp (ref "C31")
      (value "18p")
      (footprint "eagle-import:C0603")
      (libsource (lib "eagle-import") (part "C-EUC0603"))
    )
    (comp (ref "C32")
      (value "100n")
      (footprint "eagle-import:C0603")
      (libsource (lib "eagle-import") (part "C-EUC0603"))
    )
    (comp (ref "C33")
      (value "10n")
      (footprint "eagle-import:C0805")
      (libsource (lib "eagle-import") (part "C-EUC0805"))
    )
    (comp (ref "C34")
      (value "10n")
      (footprint "eagle-import:C0805")
      (libsource (lib "eagle-import") (part "C-EUC0805"))
    )
    (comp (ref "C35")
      (value "1u")
      (footprint "eagle-import:C0805")
      (libsource (lib "eagle-import") (part "C-EUC0805"))
    )
    (comp (ref "C36")
      (value "100p")
      (footprint "eagle-import:C0805")
      (libsource (lib "eagle-import") (part "C-EUC0805"))
    )
    (comp (ref "C37")
      (value "100n")
      (footprint "eagle-import:C0603")
      (libsource (lib "eagle-import") (part "C-EUC0603"))
    )
    (comp (ref "C38")
      (value "3n3")
      (footprint "eagle-import:C0805")
      (libsource (lib "eagle-import") (part "C-EUC0805"))
    )
    (comp (ref "C39")
      (value "3n3")
      (footprint "eagle-import:C0805")
      (libsource (lib "eagle-import") (part "C-EUC0805"))
    )
    (comp (ref "C40")
      (value "3n3")
      (footprint "eagle-import:C0805")
      (libsource (lib "eagle-import") (part "C-EUC0805"))
    )
    (comp (ref "C41")
      (value "3n3")
      (footprint "eagle-import:C0805")
      (libsource (lib "eagle-import") (part "C-EUC0805"))
    )
    (comp (ref "FB1")
      (value "60R@100MHz")
      (footprint "eagle-import:BEAD0603")
      (libsource (lib "eagle-import") (part "FERRITE_BEAD0603"))
    )
    (comp (ref "IC6")
      (value "TPD4E001DRLR")
      (footprint "eagle-import:DRL6")
      (libsource (lib "eagle-import") (part "TPD4E001-DRL"))
    )
    (comp (ref "IC7")
      (value "MAX5715BAUD+")
      (footprint "eagle-import:21-0066J_14")
      (libsource (lib "eagle-import") (part "MAX5715BAUD+"))
    )
    (comp (ref "IC8")
      (value "STM32F373C8T6")
      (footprint "eagle-import:LQFP-48")
      (libsource (lib "eagle-import") (part "STM32F373C8T6"))
    )
    (comp (ref "ISET1")
      (value "TEST-PIN_0.9MM")
      (footprint "eagle-import:TEST-PIN_0.9MM")
      (libsource (lib "eagle-import") (part "TEST-PIN_0.9MM"))
    )
    (comp (ref "I_SET1")
      (value "JP2-NOCUT")
      (footprint "eagle-import:JP2-NOCUT")
      (libsource (lib "eagle-import") (part "JP2-NOCUT"))
    )
    (comp (ref "I_SET2")
      (value "JP2-NOCUT")
      (footprint "eagle-import:JP2-NOCUT")
      (libsource (lib "eagle-import") (part "JP2-NOCUT"))
    )
    (comp (ref "JP1")
      (value "JUMPER-2PIN-2MM")
      (footprint "eagle-import:2MM-2")
      (libsource (lib "eagle-import") (part "JUMPER-2PIN-2MM"))
    )
    (comp (ref "JP2")
      (value "JP2-NOCUT")
      (footprint "eagle-import:JP2-NOCUT")
      (libsource (lib "eagle-import") (part "JP2-NOCUT"))
    )
    (comp (ref "JP3")
      (value "JP2-NOCUT")
      (footprint "eagle-import:JP2-NOCUT")
      (libsource (lib "eagle-import") (part "JP2-NOCUT"))
    )
    (comp (ref "JP4")
      (value "JP2-CUT")
      (footprint "eagle-import:JP2-CUT")
      (libsource (lib "eagle-import") (part "JP2-CUT"))
    )
    (comp (ref "JP5")
      (value "JP2-NOCUT")
      (footprint "eagle-import:JP2-NOCUT")
      (libsource (lib "eagle-import") (part "JP2-NOCUT"))
    )
    (comp (ref "NTC1")
      (value "NTCS0805E3103JMT")
      (footprint "eagle-import:R_0805")
      (libsource (lib "eagle-import") (part "NTCR_0805"))
    )
    (comp (ref "NTC2")
      (value "NTCS0805E3103JMT")
      (footprint "eagle-import:R_0805")
      (libsource (lib "eagle-import") (part "NTCR_0805"))
    )
    (comp (ref "OE#1")
      (value "JP2-NOCUT")
      (footprint "eagle-import:JP2-NOCUT")
      (libsource (lib "eagle-import") (part "JP2-NOCUT"))
    )
    (comp (ref "OE#2")
      (value "JP2-NOCUT")
      (footprint "eagle-import:JP2-NOCUT")
      (libsource (lib "eagle-import") (part "JP2-NOCUT"))
    )
    (comp (ref "R14")
      (value "10K")
      (footprint "eagle-import:R0805")
      (libsource (lib "eagle-import") (part "R-EU_R0805"))
    )
    (comp (ref "R15")
      (value "10K")
      (footprint "eagle-import:R0805")
      (libsource (lib "eagle-import") (part "R-EU_R0805"))
    )
    (comp (ref "R16")
      (value "3K3")
      (footprint "eagle-import:R0805")
      (libsource (lib "eagle-import") (part "R-EU_R0805"))
    )
    (comp (ref "R17")
      (value "3K3")
      (footprint "eagle-import:R0805")
      (libsource (lib "eagle-import") (part "R-EU_R0805"))
    )
    (comp (ref "R18")
      (value "1K")
      (footprint "eagle-import:R0805")
      (libsource (lib "eagle-import") (part "R-EU_R0805"))
    )
    (comp (ref "R19")
      (value "1K")
      (footprint "eagle-import:R0805")
      (libsource (lib "eagle-import") (part "R-EU_R0805"))
    )
    (comp (ref "R20")
      (value "1K")
      (footprint "eagle-import:R0805")
      (libsource (lib "eagle-import") (part "R-EU_R0805"))
    )
    (comp (ref "R21")
      (value "1K")
      (footprint "eagle-import:R0805")
      (libsource (lib "eagle-import") (part "R-EU_R0805"))
    )
    (comp (ref "RN2")
      (value "DR1206-33R-4/8")
      (footprint "eagle-import:CAY16")
      (libsource (lib "eagle-import") (part "R_ARRAY4"))
    )
    (comp (ref "SH2")
      (value "SHORTNOHOLE")
      (footprint "eagle-import:SHORT_NOHOLE")
      (libsource (lib "eagle-import") (part "SHORTNOHOLE"))
    )
    (comp (ref "U_SET1")
      (value "JP2-NOCUT")
      (footprint "eagle-import:JP2-NOCUT")
      (libsource (lib "eagle-import") (part "JP2-NOCUT"))
    )
    (comp (ref "U_SET2")
      (value "JP2-NOCUT")
      (footprint "eagle-import:JP2-NOCUT")
      (libsource (lib "eagle-import") (part "JP2-NOCUT"))
    )
    (comp (ref "X3")
      (value "22-23-2061")
      (footprint "eagle-import:22-23-2061")
      (fields (field (name "MF") "MOLEX"))
      (libsource (lib "eagle-import") (part "22-23-2061"))
    )
    (comp (ref "Y1")
      (value "LF XTAL026392")
      (footprint "eagle-import:12SMX(B)")
      (libsource (lib "eagle-import") (part "XTAL7.5X5.1-B"))
    )
  )
  (nets
    (net (code "1") (name "+3V3") (class "Default")
      (node (ref "C18") (pin "2") (pinfunction "2_2") (pintype "passive"))
      (node (ref "C21") (pin "1") (pinfunction "1_1") (pintype "passive"))
      (node (ref "C24") (pin "1") (pinfunction "1_1") (pintype "passive"))
      (node (ref "C25") (pin "2") (pinfunction "2_2") (pintype "passive"))
      (node (ref "C26") (pin "1") (pinfunction "1_1") (pintype "passive"))
      (node (ref "C27") (pin "1") (pinfunction "1_1") (pintype "passive"))
      (node (ref "C28") (pin "2") (pinfunction "2_2") (pintype "passive"))
      (node (ref "C29") (pin "2") (pinfunction "2_2") (pintype "passive"))
      (node (ref "C37") (pin "2") (pinfunction "2_2") (pintype "passive"))
      (node (ref "C63") (pin "1") (pinfunction "1_1") (pintype "passive"))
      (node (ref "C8") (pin "2") (pinfunction "2_2") (pintype "passive"))
      (node (ref "FB1") (pin "P$1") (pinfunction "1_P$1") (pintype "passive"))
      (node (ref "IC1") (pin "16") (pinfunction "VDD2_16") (pintype "passive"))
      (node (ref "IC11") (pin "4") (pinfunction "V+_4") (pintype "power_in"))
      (node (ref "IC3") (pin "10") (pinfunction "EN2_10") (pintype "input"))
      (node (ref "IC3") (pin "16") (pinfunction "VDD2_16") (pintype "passive"))
      (node (ref "IC5") (pin "5") (pinfunction "OUT_5") (pintype "passive"))
      (node (ref "IC6") (pin "6") (pinfunction "VCC_6") (pintype "passive"))
      (node (ref "IC7") (pin "13") (pinfunction "VDDIO_13") (pintype "passive"))
      (node (ref "IC7") (pin "7") (pinfunction "VDD_7") (pintype "passive"))
      (node (ref "IC8") (pin "17") (pinfunction "VDD_2_17") (pintype "passive"))
      (node (ref "IC8") (pin "48") (pinfunction "VDD_1_48") (pintype "bidirectional"))
      (node (ref "JP1") (pin "1") (pinfunction "1_1") (pintype "passive"))
      (node (ref "JP4") (pin "1") (pinfunction "1_1") (pintype "passive"))
      (node (ref "NTC1") (pin "1") (pinfunction "P$1_1") (pintype "bidirectional"))
      (node (ref "NTC2") (pin "1") (pinfunction "P$1_1") (pintype "bidirectional"))
      (node (ref "Q4") (pin "2") (pinfunction "S_2") (pintype "passive"))
      (node (ref "Q8") (pin "2") (pinfunction "S_2") (pintype "passive"))
    )
    (net (code "2") (name "+8V") (class "Default")
      (node (ref "C14") (pin "1") (pinfunction "1_1") (pintype "passive"))
      (node (ref "C22") (pin "2") (pinfunction "2_2") (pintype "passive"))
      (node (ref "C44") (pin "1") (pinfunction "1_1") (pintype "passive"))
      (node (ref "C62") (pin "1") (pinfunction "1_1") (pintype "passive"))
      (node (ref "C67") (pin "1") (pinfunction "1_1") (pintype "passive"))
      (node (ref "IC10") (pin "3") (pinfunction "VIN_3") (pintype "passive"))
      (node (ref "IC12") (pin "3") (pinfunction "VIN_3") (pintype "passive"))
      (node (ref "IC5") (pin "1") (pinfunction "IN_1") (pintype "input"))
      (node (ref "IC5") (pin "3") (pinfunction "ON/~{OFF}_3") (pintype "input"))
      (node (ref "IC9") (pin "8") (pinfunction "V+_8") (pintype "power_in"))
      (node (ref "R4") (pin "1") (pinfunction "1_1") (pintype "passive"))
    )
    (net (code "3") (name "+VAUX") (class "Default")
      (node (ref "X2") (pin "2") (pinfunction "1_2") (pintype "passive"))
    )
    (net (code "4") (name "-8V") (class "Default")
      (node (ref "C5") (pin "1") (pinfunction "1_1") (pintype "passive"))
      (node (ref "C64") (pin "2") (pinfunction "2_2") (pintype "passive"))
      (node (ref "IC9") (pin "4") (pinfunction "V-_4") (pintype "power_in"))
      (node (ref "R2") (pin "1") (pinfunction "1_1") (pintype "passive"))
    )
    (net (code "5") (name "AGND") (class "Default")
      (node (ref "C36") (pin "1") (pinfunction "1_1") (pintype "passive"))
      (node (ref "IC8") (pin "23") (pinfunction "VSSSD/VREFSD-_23") (pintype "passive"))
      (node (ref "IC8") (pin "8") (pinfunction "VSSA/VREF-_8") (pintype "passive"))
      (node (ref "SH2") (pin "1") (pinfunction "GND_A_1") (pintype "bidirectional"))
    )
    (net (code "6") (name "BOOT0") (class "Default")
      (node (ref "IC3") (pin "13") (pinfunction "B2_13") (pintype "output"))
      (node (ref "IC8") (pin "44") (pinfunction "BOOT0_44") (pintype "input"))
      (node (ref "JP1") (pin "2") (pinfunction "2_2") (pintype "passive"))
      (node (ref "R14") (pin "2") (pinfunction "2_2") (pintype "passive"))
    )
    (net (code "7") (name "CC#1") (class "Default")
      (node (ref "IC11") (pin "7") (pinfunction "OUT_7") (pintype "output"))
      (node (ref "IC8") (pin "3") (pinfunction "PC14-OSC32_IN_3") (pintype "bidirectional"))
    )
    (net (code "8") (name "CC#2") (class "Default")
      (node (ref "IC11") (pin "1") (pinfunction "OUT_1") (pintype "output"))
      (node (ref "IC8") (pin "4") (pinfunction "PC15-OSC32_OUT_4") (pintype "bidirectional"))
    )
    (net (code "9") (name "CC_LED#1") (class "Default")
      (node (ref "IC8") (pin "2") (pinfunction "PC13_2") (pintype "bidirectional"))
      (node (ref "LED1") (pin "RED") (pinfunction "AR_RED") (pintype "passive"))
      (node (ref "Q4") (pin "1") (pinfunction "G_1") (pintype "passive"))
    )
    (net (code "10") (name "CC_LED#2") (class "Default")
      (node (ref "IC8") (pin "11") (pinfunction "PA1_11") (pintype "bidirectional"))
      (node (ref "LED2") (pin "RED") (pinfunction "AR_RED") (pintype "passive"))
      (node (ref "Q8") (pin "1") (pinfunction "G_1") (pintype "passive"))
    )
    (net (code "11") (name "DAC_MOSI") (class "Default")
      (node (ref "IC7") (pin "9") (pinfunction "DIN_9") (pintype "input"))
      (node (ref "IC8") (pin "35") (pinfunction "PF6_35") (pintype "bidirectional"))
    )
    (net (code "12") (name "DAC_NSS") (class "Default")
      (node (ref "IC7") (pin "11") (pinfunction "CSB_11") (pintype "input"))
      (node (ref "IC8") (pin "14") (pinfunction "PA4_14") (pintype "bidirectional"))
    )
    (net (code "13") (name "DAC_SCLK") (class "Default")
      (node (ref "IC7") (pin "10") (pinfunction "SCLK_10") (pintype "input"))
      (node (ref "IC8") (pin "15") (pinfunction "PA5_15") (pintype "bidirectional"))
    )
    (net (code "14") (name "DC_OUT+") (class "Default")
      (node (ref "C3") (pin "2") (pinfunction "2_2") (pintype "passive"))
      (node (ref "C42") (pin "+") (pinfunction "+_+") (pintype "passive"))
      (node (ref "C45") (pin "1") (pinfunction "1_1") (pintype "passive"))
      (node (ref "C46") (pin "1") (pinfunction "1_1") (pintype "passive"))
      (node (ref "C6") (pin "1") (pinfunction "1_1") (pintype "passive"))
      (node (ref "C65") (pin "+") (pinfunction "+_+") (pintype "passive"))
      (node (ref "C68") (pin "1") (pinfunction "1_1") (pintype "passive"))
      (node (ref "C69") (pin "1") (pinfunction "1_1") (pintype "passive"))
      (node (ref "C9") (pin "1") (pinfunction "1_1") (pintype "passive"))
      (node (ref "IC10") (pin "6") (pinfunction "IVINN_6") (pintype "input"))
      (node (ref "IC10") (pin "7") (pinfunction "IVINP_7") (pintype "input"))
      (node (ref "IC12") (pin "6") (pinfunction "IVINN_6") (pintype "input"))
      (node (ref "IC12") (pin "7") (pinfunction "IVINP_7") (pintype "input"))
      (node (ref "IC2") (pin "2") (pinfunction "VIN_2") (pintype "power_in"))
      (node (ref "L1") (pin "4") (pinfunction "2_4") (pintype "passive"))
      (node (ref "Q1") (pin "2") (pinfunction "D_2") (pintype "passive"))
      (node (ref "Q5") (pin "2") (pinfunction "D_2") (pintype "passive"))
      (node (ref "R3") (pin "2") (pinfunction "2_2") (pintype "passive"))
      (node (ref "ZD1") (pin "C") (pinfunction "C_C") (pintype "passive"))
    )
    (net (code "15") (name "DC_OUT-") (class "Default")
      (node (ref "C2") (pin "1") (pinfunction "1_1") (pintype "passive"))
      (node (ref "C42") (pin "-") (pinfunction "-_-") (pintype "passive"))
      (node (ref "C45") (pin "2") (pinfunction "2_2") (pintype "passive"))
      (node (ref "C46") (pin "2") (pinfunction "2_2") (pintype "passive"))
      (node (ref "C51") (pin "2") (pinfunction "2_2") (pintype "passive"))
      (node (ref "C53") (pin "2") (pinfunction "2_2") (pintype "passive"))
      (node (ref "C54") (pin "2") (pinfunction "2_2") (pintype "passive"))
      (node (ref "C55") (pin "-") (pinfunction "-_-") (pintype "passive"))
      (node (ref "C56") (pin "-") (pinfunction "-_-") (pintype "passive"))
      (node (ref "C57") (pin "2") (pinfunction "2_2") (pintype "passive"))
      (node (ref "C65") (pin "-") (pinfunction "-_-") (pintype "passive"))
      (node (ref "C68") (pin "2") (pinfunction "2_2") (pintype "passive"))
      (node (ref "C69") (pin "2") (pinfunction "2_2") (pintype "passive"))
      (node (ref "C74") (pin "2") (pinfunction "2_2") (pintype "passive"))
      (node (ref "C76") (pin "2") (pinfunction "2_2") (pintype "passive"))
      (node (ref "C77") (pin "2") (pinfunction "2_2") (pintype "passive"))
      (node (ref "C78") (pin "-") (pinfunction "-_-") (pintype "passive"))
      (node (ref "C79") (pin "-") (pinfunction "-_-") (pintype "passive"))
      (node (ref "C80") (pin "2") (pinfunction "2_2") (pintype "passive"))
      (node (ref "CH1") (pin "GND") (pinfunction "GND_GND") (pintype "bidirectional"))
      (node (ref "CH2") (pin "GND") (pinfunction "GND_GND") (pintype "bidirectional"))
      (node (ref "D4") (pin "A") (pinfunction "A_A") (pintype "passive"))
      (node (ref "D6") (pin "A") (pinfunction "A_A") (pintype "passive"))
      (node (ref "J3") (pin "1") (pinfunction "1_1") (pintype "passive"))
      (node (ref "J3") (pin "1.1") (pinfunction "1_1.1") (pintype "passive"))
      (node (ref "J5") (pin "1") (pinfunction "1_1") (pintype "passive"))
      (node (ref "J5") (pin "1.1") (pinfunction "1_1.1") (pintype "passive"))
      (node (ref "L1") (pin "2") (pinfunction "2_2") (pintype "passive"))
      (node (ref "Q2") (pin "3") (pinfunction "S_3") (pintype "passive"))
      (node (ref "Q6") (pin "3") (pinfunction "S_3") (pintype "passive"))
      (node (ref "R31") (pin "1") (pinfunction "1_1") (pintype "passive"))
      (node (ref "R42") (pin "2") (pinfunction "2_2") (pintype "passive"))
      (node (ref "R54") (pin "1") (pinfunction "1_1") (pintype "passive"))
      (node (ref "R65") (pin "2") (pinfunction "2_2") (pintype "passive"))
      (node (ref "SH1") (pin "2") (pinfunction "GND_B_2") (pintype "bidirectional"))
      (node (ref "SH3") (pin "1") (pinfunction "GND_A_1") (pintype "bidirectional"))
      (node (ref "SH4") (pin "1") (pinfunction "GND_A_1") (pintype "bidirectional"))
      (node (ref "X4") (pin "1") (pinfunction "1_1") (pintype "passive"))
      (node (ref "X4") (pin "10") (pinfunction "1_10") (pintype "passive"))
      (node (ref "X4") (pin "2") (pinfunction "1_2") (pintype "passive"))
      (node (ref "X4") (pin "3") (pinfunction "1_3") (pintype "passive"))
      (node (ref "X4") (pin "4") (pinfunction "1_4") (pintype "passive"))
      (node (ref "X4") (pin "5") (pinfunction "1_5") (pintype "passive"))
      (node (ref "X4") (pin "6") (pinfunction "1_6") (pintype "passive"))
      (node (ref "X4") (pin "7") (pinfunction "1_7") (pintype "passive"))
      (node (ref "X4") (pin "8") (pinfunction "1_8") (pintype "passive"))
      (node (ref "X4") (pin "9") (pinfunction "1_9") (pintype "passive"))
      (node (ref "ZD1") (pin "A") (pinfunction "A_A") (pintype "passive"))
      (node (ref "ZD2") (pin "A") (pinfunction "A_A") (pintype "passive"))
      (node (ref "ZD3") (pin "A") (pinfunction "A_A") (pintype "passive"))
    )
    (net (code "16") (name "DIB_5V") (class "Default")
      (node (ref "X2") (pin "23") (pinfunction "1_23") (pintype "passive"))
      (node (ref "X2") (pin "24") (pinfunction "1_24") (pintype "passive"))
    )
    (net (code "17") (name "DIB_12V") (class "Default")
      (node (ref "X2") (pin "21") (pinfunction "1_21") (pintype "passive"))
      (node (ref "X2") (pin "22") (pinfunction "1_22") (pintype "passive"))
    )
    (net (code "18") (name "DIB_A0") (class "Default")
      (node (ref "IC4") (pin "1") (pinfunction "A0_1") (pintype "input"))
      (node (ref "R13") (pin "2") (pinfunction "2_2") (pintype "passive"))
      (node (ref "X2") (pin "17") (pinfunction "1_17") (pintype "passive"))
    )
    (net (code "19") (name "DIB_A1") (class "Default")
      (node (ref "IC4") (pin "2") (pinfunction "A1_2") (pintype "input"))
      (node (ref "R12") (pin "2") (pinfunction "2_2") (pintype "passive"))
      (node (ref "X2") (pin "19") (pinfunction "1_19") (pintype "passive"))
    )
    (net (code "20") (name "DIB_A2") (class "Default")
      (node (ref "IC4") (pin "3") (pinfunction "A2_3") (pintype "input"))
      (node (ref "R11") (pin "2") (pinfunction "2_2") (pintype "passive"))
      (node (ref "X2") (pin "18") (pinfunction "1_18") (pintype "passive"))
    )
    (net (code "21") (name "DIB_BOOT0") (class "Default")
      (node (ref "IC3") (pin "4") (pinfunction "A2_4") (pintype "input"))
      (node (ref "X2") (pin "26") (pinfunction "1_26") (pintype "passive"))
    )
    (net (code "22") (name "DIB_CSA") (class "Default")
      (node (ref "IC1") (pin "5") (pinfunction "A4_5") (pintype "input"))
      (node (ref "X2") (pin "9") (pinfunction "1_9") (pintype "passive"))
    )
    (net (code "23") (name "DIB_CSB") (class "Default")
      (node (ref "X2") (pin "12") (pinfunction "1_12") (pintype "passive"))
    )
    (net (code "24") (name "DIB_IRQ") (class "Default")
      (node (ref "IC1") (pin "7") (pinfunction "A6_7") (pintype "output"))
      (node (ref "X2") (pin "10") (pinfunction "1_10") (pintype "passive"))
    )
    (net (code "25") (name "DIB_MISO") (class "Default")
      (node (ref "IC1") (pin "6") (pinfunction "A5_6") (pintype "output"))
      (node (ref "X2") (pin "14") (pinfunction "1_14") (pintype "passive"))
    )
    (net (code "26") (name "DIB_MOSI") (class "Default")
      (node (ref "IC3") (pin "3") (pinfunction "A1_3") (pintype "input"))
      (node (ref "X2") (pin "15") (pinfunction "1_15") (pintype "passive"))
    )
    (net (code "27") (name "DIB_NFAULT") (class "Default")
      (node (ref "X2") (pin "3") (pinfunction "1_3") (pintype "passive"))
    )
    (net (code "28") (name "DIB_NRESET") (class "Default")
      (node (ref "IC1") (pin "2") (pinfunction "A1_2") (pintype "input"))
      (node (ref "X2") (pin "4") (pinfunction "1_4") (pintype "passive"))
    )
    (net (code "29") (name "DIB_SCL") (class "Default")
      (node (ref "IC4") (pin "6") (pinfunction "SCL_6") (pintype "bidirectional"))
      (node (ref "X2") (pin "5") (pinfunction "1_5") (pintype "passive"))
    )
    (net (code "30") (name "DIB_SCLK") (class "Default")
      (node (ref "IC1") (pin "4") (pinfunction "A3_4") (pintype "input"))
      (node (ref "X2") (pin "13") (pinfunction "1_13") (pintype "passive"))
    )
    (net (code "31") (name "DIB_SDA") (class "Default")
      (node (ref "IC4") (pin "5") (pinfunction "SDA_5") (pintype "bidirectional"))
      (node (ref "X2") (pin "8") (pinfunction "1_8") (pintype "passive"))
    )
    (net (code "32") (name "DIB_SYNC") (class "Default")
      (node (ref "IC1") (pin "3") (pinfunction "A2_3") (pintype "input"))
      (node (ref "X2") (pin "6") (pinfunction "1_6") (pintype "passive"))
    )
    (net (code "33") (name "DIB_UART_RX") (class "Default")
      (node (ref "IC3") (pin "6") (pinfunction "A4_6") (pintype "output"))
      (node (ref "X2") (pin "28") (pinfunction "1_28") (pintype "passive"))
    )
    (net (code "34") (name "DIB_UART_TX") (class "Default")
      (node (ref "IC3") (pin "5") (pinfunction "A3_5") (pintype "input"))
      (node (ref "X2") (pin "27") (pinfunction "1_27") (pintype "passive"))
    )
    (net (code "35") (name "FB1") (class "Default")
      (node (ref "IC10") (pin "11") (pinfunction "FB_11") (pintype "input"))
      (node (ref "IC11") (pin "10") (pinfunction "+IN_10") (pintype "input"))
      (node (ref "R33") (pin "1") (pinfunction "1_1") (pintype "passive"))
      (node (ref "R39") (pin "2") (pinfunction "2_2") (pintype "passive"))
      (node (ref "R41") (pin "2") (pinfunction "2_2") (pintype "passive"))
    )
    (net (code "36") (name "FB2") (class "Default")
      (node (ref "IC11") (pin "12") (pinfunction "+IN_12") (pintype "input"))
      (node (ref "IC12") (pin "11") (pinfunction "FB_11") (pintype "input"))
      (node (ref "R56") (pin "1") (pinfunction "1_1") (pintype "passive"))
      (node (ref "R62") (pin "2") (pinfunction "2_2") (pintype "passive"))
      (node (ref "R64") (pin "2") (pinfunction "2_2") (pintype "passive"))
    )
    (net (code "37") (name "GND") (class "Default")
      (node (ref "C12") (pin "2") (pinfunction "2_2") (pintype "passive"))
      (node (ref "C13") (pin "2") (pinfunction "2_2") (pintype "passive"))
      (node (ref "C14") (pin "2") (pinfunction "2_2") (pintype "passive"))
      (node (ref "C15") (pin "2") (pinfunction "2_2") (pintype "passive"))
      (node (ref "C16") (pin "1") (pinfunction "1_1") (pintype "passive"))
      (node (ref "C18") (pin "1") (pinfunction "1_1") (pintype "passive"))
      (node (ref "C19") (pin "1") (pinfunction "1_1") (pintype "passive"))
      (node (ref "C21") (pin "2") (pinfunction "2_2") (pintype "passive"))
      (node (ref "C22") (pin "1") (pinfunction "1_1") (pintype "passive"))
      (node (ref "C23") (pin "1") (pinfunction "1_1") (pintype "passive"))
      (node (ref "C24") (pin "2") (pinfunction "2_2") (pintype "passive"))
      (node (ref "C25") (pin "1") (pinfunction "1_1") (pintype "passive"))
      (node (ref "C26") (pin "2") (pinfunction "2_2") (pintype "passive"))
      (node (ref "C27") (pin "2") (pinfunction "2_2") (pintype "passive"))
      (node (ref "C28") (pin "1") (pinfunction "1_1") (pintype "passive"))
      (node (ref "C29") (pin "1") (pinfunction "1_1") (pintype "passive"))
      (node (ref "C30") (pin "1") (pinfunction "1_1") (pintype "passive"))
      (node (ref "C31") (pin "1") (pinfunction "1_1") (pintype "passive"))
      (node (ref "C32") (pin "1") (pinfunction "1_1") (pintype "passive"))
      (node (ref "C33") (pin "1") (pinfunction "1_1") (pintype "passive"))
      (node (ref "C34") (pin "1") (pinfunction "1_1") (pintype "passive"))
      (node (ref "C35") (pin "1") (pinfunction "1_1") (pintype "passive"))
      (node (ref "C37") (pin "1") (pinfunction "1_1") (pintype "passive"))
      (node (ref "C38") (pin "1") (pinfunction "1_1") (pintype "passive"))
      (node (ref "C39") (pin "1") (pinfunction "1_1") (pintype "passive"))
      (node (ref "C4") (pin "2") (pinfunction "2_2") (pintype "passive"))
      (node (ref "C40") (pin "1") (pinfunction "1_1") (pintype "passive"))
      (node (ref "C41") (pin "1") (pinfunction "1_1") (pintype "passive"))
      (node (ref "C44") (pin "2") (pinfunction "2_2") (pintype "passive"))
      (node (ref "C47") (pin "2") (pinfunction "2_2") (pintype "passive"))
      (node (ref "C49") (pin "2") (pinfunction "2_2") (pintype "passive"))
      (node (ref "C5") (pin "2") (pinfunction "2_2") (pintype "passive"))
      (node (ref "C58") (pin "1") (pinfunction "1_1") (pintype "passive"))
      (node (ref "C6") (pin "2") (pinfunction "2_2") (pintype "passive"))
      (node (ref "C60") (pin "1") (pinfunction "1_1") (pintype "passive"))
      (node (ref "C62") (pin "2") (pinfunction "2_2") (pintype "passive"))
      (node (ref "C63") (pin "2") (pinfunction "2_2") (pintype "passive"))
      (node (ref "C64") (pin "1") (pinfunction "1_1") (pintype "passive"))
      (node (ref "C67") (pin "2") (pinfunction "2_2") (pintype "passive"))
      (node (ref "C70") (pin "2") (pinfunction "2_2") (pintype "passive"))
      (node (ref "C72") (pin "2") (pinfunction "2_2") (pintype "passive"))
      (node (ref "C8") (pin "1") (pinfunction "1_1") (pintype "passive"))
      (node (ref "C81") (pin "1") (pinfunction "1_1") (pintype "passive"))
      (node (ref "C83") (pin "1") (pinfunction "1_1") (pintype "passive"))
      (node (ref "C9") (pin "2") (pinfunction "2_2") (pintype "passive"))
      (node (ref "D2") (pin "A") (pinfunction "A_A") (pintype "passive"))
      (node (ref "GND") (pin "1") (pinfunction "P$1_1") (pintype "bidirectional"))
      (node (ref "IC1") (pin "9") (pinfunction "GND2_9") (pintype "passive"))
      (node (ref "IC10") (pin "12") (pinfunction "GND_12") (pintype "passive"))
      (node (ref "IC10") (pin "21") (pinfunction "SYNC_21") (pintype "input"))
      (node (ref "IC10") (pin "23") (pinfunction "GND_23") (pintype "passive"))
      (node (ref "IC10") (pin "28") (pinfunction "GND_28") (pintype "passive"))
      (node (ref "IC10") (pin "TP") (pinfunction "GND_PAD_TP") (pintype "passive"))
      (node (ref "IC11") (pin "11") (pinfunction "V-_11") (pintype "power_in"))
      (node (ref "IC12") (pin "12") (pinfunction "GND_12") (pintype "passive"))
      (node (ref "IC12") (pin "21") (pinfunction "SYNC_21") (pintype "input"))
      (node (ref "IC12") (pin "23") (pinfunction "GND_23") (pintype "passive"))
      (node (ref "IC12") (pin "28") (pinfunction "GND_28") (pintype "passive"))
      (node (ref "IC12") (pin "TP") (pinfunction "GND_PAD_TP") (pintype "passive"))
      (node (ref "IC2") (pin "9") (pinfunction "GND_9") (pintype "passive"))
      (node (ref "IC2") (pin "TP") (pinfunction "TP_TP") (pintype "passive"))
      (node (ref "IC3") (pin "15") (pinfunction "GND2_15") (pintype "passive"))
      (node (ref "IC3") (pin "9") (pinfunction "GND2_2_9") (pintype "passive"))
      (node (ref "IC5") (pin "2") (pinfunction "GND_2") (pintype "passive"))
      (node (ref "IC6") (pin "3") (pinfunction "GND_3") (pintype "power_in"))
      (node (ref "IC7") (pin "4") (pinfunction "GND_4") (pintype "passive"))
      (node (ref "IC8") (pin "47") (pinfunction "VSS_1_47") (pintype "bidirectional"))
      (node (ref "JP2") (pin "2") (pinfunction "2_2") (pintype "passive"))
      (node (ref "R10") (pin "1") (pinfunction "1_1") (pintype "passive"))
      (node (ref "R14") (pin "1") (pinfunction "1_1") (pintype "passive"))
      (node (ref "R15") (pin "1") (pinfunction "1_1") (pintype "passive"))
      (node (ref "R16") (pin "2") (pinfunction "2_2") (pintype "passive"))
      (node (ref "R17") (pin "2") (pinfunction "2_2") (pintype "passive"))
      (node (ref "R22") (pin "1") (pinfunction "1_1") (pintype "passive"))
      (node (ref "R26") (pin "1") (pinfunction "1_1") (pintype "passive"))
      (node (ref "R35") (pin "1") (pinfunction "1_1") (pintype "passive"))
      (node (ref "R38") (pin "1") (pinfunction "1_1") (pintype "passive"))
      (node (ref "R39") (pin "1") (pinfunction "1_1") (pintype "passive"))
      (node (ref "R40") (pin "1") (pinfunction "1_1") (pintype "passive"))
      (node (ref "R44") (pin "1") (pinfunction "1_1") (pintype "passive"))
      (node (ref "R45") (pin "1") (pinfunction "1_1") (pintype "passive"))
      (node (ref "R49") (pin "1") (pinfunction "1_1") (pintype "passive"))
      (node (ref "R5") (pin "1") (pinfunction "1_1") (pintype "passive"))
      (node (ref "R58") (pin "1") (pinfunction "1_1") (pintype "passive"))
      (node (ref "R6") (pin "1") (pinfunction "1_1") (pintype "passive"))
      (node (ref "R61") (pin "1") (pinfunction "1_1") (pintype "passive"))
      (node (ref "R62") (pin "1") (pinfunction "1_1") (pintype "passive"))
      (node (ref "R63") (pin "1") (pinfunction "1_1") (pintype "passive"))
      (node (ref "R67") (pin "1") (pinfunction "1_1") (pintype "passive"))
      (node (ref "R8") (pin "1") (pinfunction "1_1") (pintype "passive"))
      (node (ref "SH1") (pin "1") (pinfunction "GND_A_1") (pintype "bidirectional"))
      (node (ref "SH2") (pin "2") (pinfunction "GND_B_2") (pintype "bidirectional"))
      (node (ref "SH3") (pin "2") (pinfunction "GND_B_2") (pintype "bidirectional"))
      (node (ref "SH4") (pin "2") (pinfunction "GND_B_2") (pintype "bidirectional"))
      (node (ref "TR1") (pin "4") (pinfunction "4_4") (pintype "passive"))
      (node (ref "X3") (pin "3") (pinfunction "S_3") (pintype "passive"))
    )
    (net (code "38") (name "GNDIO") (class "Default")
      (node (ref "C17") (pin "2") (pinfunction "2_2") (pintype "passive"))
      (node (ref "C20") (pin "1") (pinfunction "1_1") (pintype "passive"))
      (node (ref "C7") (pin "2") (pinfunction "2_2") (pintype "passive"))
      (node (ref "IC1") (pin "8") (pinfunction "GND1_8") (pintype "passive"))
      (node (ref "IC3") (pin "2") (pinfunction "GND1_2_2") (pintype "passive"))
      (node (ref "IC3") (pin "8") (pinfunction "GND1_8") (pintype "passive"))
      (node (ref "IC4") (pin "4") (pinfunction "GND_4") (pintype "passive"))
      (node (ref "IC4") (pin "7") (pinfunction "WP_7") (pintype "input"))
      (node (ref "X2") (pin "11") (pinfunction "1_11") (pintype "passive"))
      (node (ref "X2") (pin "16") (pinfunction "1_16") (pintype "passive"))
      (node (ref "X2") (pin "20") (pinfunction "1_20") (pintype "passive"))
      (node (ref "X2") (pin "25") (pinfunction "1_25") (pintype "passive"))
      (node (ref "X2") (pin "7") (pinfunction "1_7") (pintype "passive"))
    )
    (net (code "39") (name "INTVCC1") (class "Default")
      (node (ref "C49") (pin "1") (pinfunction "1_1") (pintype "passive"))
      (node (ref "D3") (pin "A") (pinfunction "A_A") (pintype "passive"))
      (node (ref "IC10") (pin "2") (pinfunction "INTVCC_2") (pintype "passive"))
      (node (ref "R36") (pin "1") (pinfunction "1_1") (pintype "passive"))
      (node (ref "R37") (pin "2") (pinfunction "2_2") (pintype "passive"))
    )
    (net (code "40") (name "INTVCC2") (class "Default")
      (node (ref "C72") (pin "1") (pinfunction "1_1") (pintype "passive"))
      (node (ref "D5") (pin "A") (pinfunction "A_A") (pintype "passive"))
      (node (ref "IC12") (pin "2") (pinfunction "INTVCC_2") (pintype "passive"))
      (node (ref "R59") (pin "1") (pinfunction "1_1") (pintype "passive"))
      (node (ref "R60") (pin "2") (pinfunction "2_2") (pintype "passive"))
    )
    (net (code "41") (name "IRQ") (class "Default")
      (node (ref "IC1") (pin "10") (pinfunction "B6_10") (pintype "input"))
      (node (ref "IC8") (pin "33") (pinfunction "PA12_33") (pintype "bidirectional"))
    )
    (net (code "42") (name "I_MON#1") (class "Default")
      (node (ref "C39") (pin "2") (pinfunction "2_2") (pintype "passive"))
      (node (ref "IC8") (pin "19") (pinfunction "PB1_19") (pintype "bidirectional"))
      (node (ref "R19") (pin "1") (pinfunction "1_1") (pintype "passive"))
    )
    (net (code "43") (name "I_MON#2") (class "Default")
      (node (ref "C41") (pin "2") (pinfunction "2_2") (pintype "passive"))
      (node (ref "IC8") (pin "21") (pinfunction "PE8_21") (pintype "bidirectional"))
      (node (ref "R21") (pin "1") (pinfunction "1_1") (pintype "passive"))
    )
    (net (code "44") (name "I_MON1") (class "Default")
      (node (ref "C58") (pin "2") (pinfunction "2_2") (pintype "passive"))
      (node (ref "R19") (pin "2") (pinfunction "2_2") (pintype "passive"))
      (node (ref "R32") (pin "1") (pinfunction "1_1") (pintype "passive"))
    )
    (net (code "45") (name "I_MON2") (class "Default")
      (node (ref "C81") (pin "2") (pinfunction "2_2") (pintype "passive"))
      (node (ref "R21") (pin "2") (pinfunction "2_2") (pintype "passive"))
      (node (ref "R55") (pin "1") (pinfunction "1_1") (pintype "passive"))
    )
    (net (code "46") (name "I_SET#1") (class "Default")
      (node (ref "I_SET1") (pin "1") (pinfunction "1_1") (pintype "passive"))
      (node (ref "R25") (pin "1") (pinfunction "1_1") (pintype "passive"))
    )
    (net (code "47") (name "I_SET#2") (class "Default")
      (node (ref "I_SET2") (pin "1") (pinfunction "1_1") (pintype "passive"))
      (node (ref "R48") (pin "1") (pinfunction "1_1") (pintype "passive"))
    )
    (net (code "48") (name "MISO") (class "Default")
      (node (ref "IC1") (pin "11") (pinfunction "B5_11") (pintype "input"))
      (node (ref "IC8") (pin "30") (pinfunction "PA9_30") (pintype "bidirectional"))
    )
    (net (code "49") (name "MOSI") (class "Default")
      (node (ref "IC8") (pin "31") (pinfunction "PA10_31") (pintype "bidirectional"))
      (node (ref "RN1") (pin "5") (pinfunction "2_5") (pintype "passive"))
    )
    (net (code "50") (name "NSS") (class "Default")
      (node (ref "IC8") (pin "32") (pinfunction "PA11_32") (pintype "bidirectional"))
      (node (ref "RN1") (pin "6") (pinfunction "2_6") (pintype "passive"))
    )
    (net (code "51") (name "Net-(C4-Pad1)") (class "Default")
      (node (ref "C4") (pin "1") (pinfunction "1_1") (pintype "passive"))
      (node (ref "D1") (pin "A") (pinfunction "A_A") (pintype "passive"))
      (node (ref "R2") (pin "2") (pinfunction "2_2") (pintype "passive"))
    )
    (net (code "52") (name "Net-(C11-Pad2)") (class "Default")
      (node (ref "C11") (pin "2") (pinfunction "2_2") (pintype "passive"))
      (node (ref "R5") (pin "2") (pinfunction "2_2") (pintype "passive"))
    )
    (net (code "53") (name "Net-(C12-Pad1)") (class "Default")
      (node (ref "C12") (pin "1") (pinfunction "1_1") (pintype "passive"))
      (node (ref "C13") (pin "1") (pinfunction "1_1") (pintype "passive"))
      (node (ref "R4") (pin "2") (pinfunction "2_2") (pintype "passive"))
      (node (ref "R7") (pin "2") (pinfunction "2_2") (pintype "passive"))
      (node (ref "TR1") (pin "3") (pinfunction "3_3") (pintype "passive"))
    )
    (net (code "54") (name "Net-(C19-Pad2)") (class "Default")
      (node (ref "C19") (pin "2") (pinfunction "2_2") (pintype "passive"))
      (node (ref "R9") (pin "1") (pinfunction "1_1") (pintype "passive"))
    )
    (net (code "55") (name "Net-(C52-Pad2)") (class "Default")
      (node (ref "C52") (pin "2") (pinfunction "2_2") (pintype "passive"))
      (node (ref "R31") (pin "2") (pinfunction "2_2") (pintype "passive"))
    )
    (net (code "56") (name "Net-(C61-Pad1)") (class "Default")
      (node (ref "C61") (pin "1") (pinfunction "1_1") (pintype "passive"))
      (node (ref "R38") (pin "2") (pinfunction "2_2") (pintype "passive"))
    )
    (net (code "57") (name "Net-(C75-Pad2)") (class "Default")
      (node (ref "C75") (pin "2") (pinfunction "2_2") (pintype "passive"))
      (node (ref "R54") (pin "2") (pinfunction "2_2") (pintype "passive"))
    )
    (net (code "58") (name "Net-(C84-Pad1)") (class "Default")
      (node (ref "C84") (pin "1") (pinfunction "1_1") (pintype "passive"))
      (node (ref "R61") (pin "2") (pinfunction "2_2") (pintype "passive"))
    )
    (net (code "59") (name "Net-(D1-PadC)") (class "Default")
      (node (ref "D1") (pin "C") (pinfunction "C_C") (pintype "passive"))
      (node (ref "TR1") (pin "2") (pinfunction "2_2") (pintype "passive"))
    )
    (net (code "60") (name "Net-(IC1-B2)") (class "Default")
      (node (ref "IC1") (pin "14") (pinfunction "B2_14") (pintype "output"))
      (node (ref "RN1") (pin "1") (pinfunction "1_1") (pintype "passive"))
    )
    (net (code "61") (name "Net-(IC1-B3)") (class "Default")
      (node (ref "IC1") (pin "13") (pinfunction "B3_13") (pintype "output"))
      (node (ref "RN1") (pin "2") (pinfunction "1_2") (pintype "passive"))
    )
    (net (code "62") (name "Net-(IC1-B4)") (class "Default")
      (node (ref "IC1") (pin "12") (pinfunction "B4_12") (pintype "output"))
      (node (ref "RN1") (pin "3") (pinfunction "1_3") (pintype "passive"))
    )
    (net (code "63") (name "Net-(IC2-BOOT)") (class "Default")
      (node (ref "C10") (pin "2") (pinfunction "2_2") (pintype "passive"))
      (node (ref "IC2") (pin "1") (pinfunction "BOOT_1") (pintype "output"))
    )
    (net (code "64") (name "Net-(IC2-COMP)") (class "Default")
      (node (ref "C16") (pin "2") (pinfunction "2_2") (pintype "passive"))
      (node (ref "IC2") (pin "8") (pinfunction "COMP_8") (pintype "output"))
      (node (ref "R9") (pin "2") (pinfunction "2_2") (pintype "passive"))
    )
    (net (code "65") (name "Net-(IC2-EN)") (class "Default")
      (node (ref "IC2") (pin "3") (pinfunction "EN_3") (pintype "input"))
      (node (ref "R3") (pin "1") (pinfunction "1_1") (pintype "passive"))
      (node (ref "R6") (pin "2") (pinfunction "2_2") (pintype "passive"))
    )
    (net (code "66") (name "Net-(IC2-PH)") (class "Default")
      (node (ref "C10") (pin "1") (pinfunction "1_1") (pintype "passive"))
      (node (ref "C11") (pin "1") (pinfunction "1_1") (pintype "passive"))
      (node (ref "D2") (pin "C") (pinfunction "C_C") (pintype "passive"))
      (node (ref "IC2") (pin "10") (pinfunction "PH_10") (pintype "input"))
      (node (ref "TR1") (pin "1") (pinfunction "1_1") (pintype "passive"))
    )
    (net (code "67") (name "Net-(IC2-RT{slash}CLK)") (class "Default")
      (node (ref "IC2") (pin "5") (pinfunction "RT/CLK_5") (pintype "input"))
      (node (ref "R8") (pin "2") (pinfunction "2_2") (pintype "passive"))
    )
    (net (code "68") (name "Net-(IC2-SS{slash}TR)") (class "Default")
      (node (ref "C15") (pin "1") (pinfunction "1_1") (pintype "passive"))
      (node (ref "IC2") (pin "4") (pinfunction "SS/TR_4") (pintype "input"))
    )
    (net (code "69") (name "Net-(IC2-VSENSE)") (class "Default")
      (node (ref "IC2") (pin "7") (pinfunction "VSENSE_7") (pintype "input"))
      (node (ref "R10") (pin "2") (pinfunction "2_2") (pintype "passive"))
      (node (ref "R7") (pin "1") (pinfunction "1_1") (pintype "passive"))
    )
    (net (code "70") (name "Net-(IC3-B1)") (class "Default")
      (node (ref "IC3") (pin "14") (pinfunction "B1_14") (pintype "output"))
      (node (ref "RN1") (pin "4") (pinfunction "1_4") (pintype "passive"))
    )
    (net (code "71") (name "Net-(IC5-BYPASS)") (class "Default")
      (node (ref "C23") (pin "2") (pinfunction "2_2") (pintype "passive"))
      (node (ref "IC5") (pin "4") (pinfunction "BYPASS_4") (pintype "passive"))
    )
    (net (code "72") (name "Net-(IC6-IO1)") (class "Default")
      (node (ref "IC6") (pin "1") (pinfunction "IO1_1") (pintype "bidirectional"))
      (node (ref "RN2") (pin "8") (pinfunction "2_8") (pintype "passive"))
      (node (ref "X3") (pin "6") (pinfunction "S_6") (pintype "passive"))
    )
    (net (code "73") (name "Net-(IC6-IO2)") (class "Default")
      (node (ref "IC6") (pin "2") (pinfunction "IO2_2") (pintype "bidirectional"))
      (node (ref "RN2") (pin "5") (pinfunction "2_5") (pintype "passive"))
      (node (ref "X3") (pin "5") (pinfunction "S_5") (pintype "passive"))
    )
    (net (code "74") (name "Net-(IC7-OUTA)") (class "Default")
      (node (ref "IC7") (pin "2") (pinfunction "OUTA_2") (pintype "output"))
      (node (ref "U_SET1") (pin "2") (pinfunction "2_2") (pintype "passive"))
    )
    (net (code "75") (name "Net-(IC7-OUTB)") (class "Default")
      (node (ref "IC7") (pin "3") (pinfunction "OUTB_3") (pintype "output"))
      (node (ref "ISET1") (pin "1") (pinfunction "P$1_1") (pintype "bidirectional"))
      (node (ref "I_SET1") (pin "2") (pinfunction "2_2") (pintype "passive"))
    )
    (net (code "76") (name "Net-(IC7-OUTC)") (class "Default")
      (node (ref "IC7") (pin "5") (pinfunction "OUTC_5") (pintype "output"))
      (node (ref "I_SET2") (pin "2") (pinfunction "2_2") (pintype "passive"))
    )
    (net (code "77") (name "Net-(IC7-OUTD)") (class "Default")
      (node (ref "IC7") (pin "6") (pinfunction "OUTD_6") (pintype "output"))
      (node (ref "U_SET2") (pin "2") (pinfunction "2_2") (pintype "passive"))
    )
    (net (code "78") (name "Net-(IC8-PB5)") (class "Default")
      (node (ref "IC8") (pin "41") (pinfunction "PB5_41") (pintype "bidirectional"))
      (node (ref "OE#2") (pin "1") (pinfunction "1_1") (pintype "passive"))
    )
    (net (code "79") (name "Net-(IC8-PB6)") (class "Default")
      (node (ref "IC8") (pin "42") (pinfunction "PB6_42") (pintype "bidirectional"))
      (node (ref "OE#1") (pin "1") (pinfunction "1_1") (pintype "passive"))
    )
    (net (code "80") (name "Net-(IC8-PF0-OSC_IN)") (class "Default")
      (node (ref "C30") (pin "2") (pinfunction "2_2") (pintype "passive"))
      (node (ref "IC8") (pin "5") (pinfunction "PF0-OSC_IN_5") (pintype "bidirectional"))
      (node (ref "Y1") (pin "3") (pinfunction "2_3") (pintype "passive"))
    )
    (net (code "81") (name "Net-(IC8-PF1-OSC_OUT)") (class "Default")
      (node (ref "C31") (pin "2") (pinfunction "2_2") (pintype "passive"))
      (node (ref "IC8") (pin "6") (pinfunction "PF1-OSC_OUT_6") (pintype "bidirectional"))
      (node (ref "Y1") (pin "1") (pinfunction "1_1") (pintype "passive"))
    )
    (net (code "82") (name "Net-(IC8-VREFSD+)") (class "Default")
      (node (ref "C36") (pin "2") (pinfunction "2_2") (pintype "passive"))
      (node (ref "IC8") (pin "25") (pinfunction "VREFSD+_25") (pintype "passive"))
      (node (ref "JP5") (pin "1") (pinfunction "1_1") (pintype "passive"))
    )
    (net (code "83") (name "Net-(IC9A-+IN)") (class "Default")
      (node (ref "IC9") (pin "3") (pinfunction "+IN_3") (pintype "input"))
      (node (ref "R48") (pin "2") (pinfunction "2_2") (pintype "passive"))
      (node (ref "R49") (pin "2") (pinfunction "2_2") (pintype "passive"))
    )
    (net (code "84") (name "Net-(IC9A--IN)") (class "Default")
      (node (ref "C66") (pin "2") (pinfunction "2_2") (pintype "passive"))
      (node (ref "IC9") (pin "2") (pinfunction "-IN_2") (pintype "input"))
      (node (ref "R45") (pin "2") (pinfunction "2_2") (pintype "passive"))
      (node (ref "R46") (pin "1") (pinfunction "1_1") (pintype "passive"))
    )
    (net (code "85") (name "Net-(IC9B-+IN)") (class "Default")
      (node (ref "IC9") (pin "5") (pinfunction "+IN_5") (pintype "input"))
      (node (ref "R25") (pin "2") (pinfunction "2_2") (pintype "passive"))
      (node (ref "R26") (pin "2") (pinfunction "2_2") (pintype "passive"))
    )
    (net (code "86") (name "Net-(IC9B--IN)") (class "Default")
      (node (ref "C43") (pin "2") (pinfunction "2_2") (pintype "passive"))
      (node (ref "IC9") (pin "6") (pinfunction "-IN_6") (pintype "input"))
      (node (ref "R22") (pin "2") (pinfunction "2_2") (pintype "passive"))
      (node (ref "R23") (pin "1") (pinfunction "1_1") (pintype "passive"))
    )
    (net (code "87") (name "Net-(IC10-BG)") (class "Default")
      (node (ref "IC10") (pin "1") (pinfunction "BG_1") (pintype "output"))
      (node (ref "R30") (pin "1") (pinfunction "1_1") (pintype "passive"))
    )
    (net (code "88") (name "Net-(IC10-BOOST)") (class "Default")
      (node (ref "C48") (pin "1") (pinfunction "1_1") (pintype "passive"))
      (node (ref "D3") (pin "C") (pinfunction "C_C") (pintype "passive"))
      (node (ref "IC10") (pin "27") (pinfunction "BOOST_27") (pintype "passive"))
    )
    (net (code "89") (name "Net-(IC10-CTRL1)") (class "Default")
      (node (ref "C43") (pin "1") (pinfunction "1_1") (pintype "passive"))
      (node (ref "IC10") (pin "14") (pinfunction "CTRL1_14") (pintype "input"))
      (node (ref "IC9") (pin "7") (pinfunction "OUT_7") (pintype "output"))
      (node (ref "R23") (pin "2") (pinfunction "2_2") (pintype "passive"))
    )
    (net (code "90") (name "Net-(IC10-ISMON)") (class "Default")
      (node (ref "IC10") (pin "19") (pinfunction "ISMON_19") (pintype "output"))
      (node (ref "R32") (pin "2") (pinfunction "2_2") (pintype "passive"))
    )
    (net (code "91") (name "Net-(IC10-PWM)") (class "Default")
      (node (ref "IC10") (pin "22") (pinfunction "PWM_22") (pintype "input"))
      (node (ref "R36") (pin "2") (pinfunction "2_2") (pintype "passive"))
    )
    (net (code "92") (name "Net-(IC10-RT)") (class "Default")
      (node (ref "IC10") (pin "20") (pinfunction "RT_20") (pintype "input"))
      (node (ref "R35") (pin "2") (pinfunction "2_2") (pintype "passive"))
    )
    (net (code "93") (name "Net-(IC10-SENSE+)") (class "Default")
      (node (ref "C59") (pin "1") (pinfunction "1_1") (pintype "passive"))
      (node (ref "IC10") (pin "17") (pinfunction "SENSE+_17") (pintype "input"))
      (node (ref "R28") (pin "1") (pinfunction "1_1") (pintype "passive"))
    )
    (net (code "94") (name "Net-(IC10-SENSE-)") (class "Default")
      (node (ref "C59") (pin "2") (pinfunction "2_2") (pintype "passive"))
      (node (ref "IC10") (pin "16") (pinfunction "SENSE-_16") (pintype "input"))
      (node (ref "R29") (pin "1") (pinfunction "1_1") (pintype "passive"))
    )
    (net (code "95") (name "Net-(IC10-SS)") (class "Default")
      (node (ref "C60") (pin "2") (pinfunction "2_2") (pintype "passive"))
      (node (ref "IC10") (pin "15") (pinfunction "SS_15") (pintype "input"))
    )
    (net (code "96") (name "Net-(IC10-SW)") (class "Default")
      (node (ref "C48") (pin "2") (pinfunction "2_2") (pintype "passive"))
      (node (ref "C52") (pin "1") (pinfunction "1_1") (pintype "passive"))
      (node (ref "D4") (pin "C") (pinfunction "C_C") (pintype "passive"))
      (node (ref "IC10") (pin "26") (pinfunction "SW_26") (pintype "output"))
      (node (ref "L2") (pin "1") (pinfunction "1_1") (pintype "passive"))
      (node (ref "Q1") (pin "3") (pinfunction "S_3") (pintype "passive"))
      (node (ref "Q2") (pin "2") (pinfunction "D_2") (pintype "passive"))
    )
    (net (code "97") (name "Net-(IC10-TG)") (class "Default")
      (node (ref "IC10") (pin "25") (pinfunction "TG_25") (pintype "output"))
      (node (ref "R24") (pin "1") (pinfunction "1_1") (pintype "passive"))
    )
    (net (code "98") (name "Net-(IC10-VC)") (class "Default")
      (node (ref "C61") (pin "2") (pinfunction "2_2") (pintype "passive"))
      (node (ref "IC10") (pin "18") (pinfunction "VC_18") (pintype "passive"))
    )
    (net (code "99") (name "Net-(IC10-~{FAULT})") (class "Default")
      (node (ref "IC10") (pin "9") (pinfunction "~{FAULT}_9") (pintype "output"))
      (node (ref "R37") (pin "1") (pinfunction "1_1") (pintype "passive"))
    )
    (net (code "100") (name "Net-(IC11A-+IN)") (class "Default")
      (node (ref "IC11") (pin "3") (pinfunction "+IN_3") (pintype "input"))
      (node (ref "R66") (pin "1") (pinfunction "1_1") (pintype "passive"))
      (node (ref "R67") (pin "2") (pinfunction "2_2") (pintype "passive"))
    )
    (net (code "101") (name "Net-(IC11A--IN)") (class "Default")
      (node (ref "IC11") (pin "13") (pinfunction "-IN_13") (pintype "input"))
      (node (ref "IC11") (pin "14") (pinfunction "OUT_14") (pintype "output"))
      (node (ref "IC11") (pin "2") (pinfunction "-IN_2") (pintype "input"))
    )
    (net (code "102") (name "Net-(IC11B-+IN)") (class "Default")
      (node (ref "IC11") (pin "5") (pinfunction "+IN_5") (pintype "input"))
      (node (ref "R43") (pin "1") (pinfunction "1_1") (pintype "passive"))
      (node (ref "R44") (pin "2") (pinfunction "2_2") (pintype "passive"))
    )
    (net (code "103") (name "Net-(IC11B--IN)") (class "Default")
      (node (ref "IC11") (pin "6") (pinfunction "-IN_6") (pintype "input"))
      (node (ref "IC11") (pin "8") (pinfunction "OUT_8") (pintype "output"))
      (node (ref "IC11") (pin "9") (pinfunction "-IN_9") (pintype "input"))
    )
    (net (code "104") (name "Net-(IC12-BG)") (class "Default")
      (node (ref "IC12") (pin "1") (pinfunction "BG_1") (pintype "output"))
      (node (ref "R53") (pin "1") (pinfunction "1_1") (pintype "passive"))
    )
    (net (code "105") (name "Net-(IC12-BOOST)") (class "Default")
      (node (ref "C71") (pin "1") (pinfunction "1_1") (pintype "passive"))
      (node (ref "D5") (pin "C") (pinfunction "C_C") (pintype "passive"))
      (node (ref "IC12") (pin "27") (pinfunction "BOOST_27") (pintype "passive"))
    )
    (net (code "106") (name "Net-(IC12-CTRL1)") (class "Default")
      (node (ref "C66") (pin "1") (pinfunction "1_1") (pintype "passive"))
      (node (ref "IC12") (pin "14") (pinfunction "CTRL1_14") (pintype "input"))
      (node (ref "IC9") (pin "1") (pinfunction "OUT_1") (pintype "output"))
      (node (ref "R46") (pin "2") (pinfunction "2_2") (pintype "passive"))
    )
    (net (code "107") (name "Net-(IC12-ISMON)") (class "Default")
      (node (ref "IC12") (pin "19") (pinfunction "ISMON_19") (pintype "output"))
      (node (ref "R55") (pin "2") (pinfunction "2_2") (pintype "passive"))
    )
    (net (code "108") (name "Net-(IC12-PWM)") (class "Default")
      (node (ref "IC12") (pin "22") (pinfunction "PWM_22") (pintype "input"))
      (node (ref "R59") (pin "2") (pinfunction "2_2") (pintype "passive"))
    )
    (net (code "109") (name "Net-(IC12-RT)") (class "Default")
      (node (ref "IC12") (pin "20") (pinfunction "RT_20") (pintype "input"))
      (node (ref "R58") (pin "2") (pinfunction "2_2") (pintype "passive"))
    )
    (net (code "110") (name "Net-(IC12-SENSE+)") (class "Default")
      (node (ref "C82") (pin "1") (pinfunction "1_1") (pintype "passive"))
      (node (ref "IC12") (pin "17") (pinfunction "SENSE+_17") (pintype "input"))
      (node (ref "R51") (pin "1") (pinfunction "1_1") (pintype "passive"))
    )
    (net (code "111") (name "Net-(IC12-SENSE-)") (class "Default")
      (node (ref "C82") (pin "2") (pinfunction "2_2") (pintype "passive"))
      (node (ref "IC12") (pin "16") (pinfunction "SENSE-_16") (pintype "input"))
      (node (ref "R52") (pin "1") (pinfunction "1_1") (pintype "passive"))
    )
    (net (code "112") (name "Net-(IC12-SS)") (class "Default")
      (node (ref "C83") (pin "2") (pinfunction "2_2") (pintype "passive"))
      (node (ref "IC12") (pin "15") (pinfunction "SS_15") (pintype "input"))
    )
    (net (code "113") (name "Net-(IC12-SW)") (class "Default")
      (node (ref "C71") (pin "2") (pinfunction "2_2") (pintype "passive"))
      (node (ref "C75") (pin "1") (pinfunction "1_1") (pintype "passive"))
      (node (ref "D6") (pin "C") (pinfunction "C_C") (pintype "passive"))
      (node (ref "IC12") (pin "26") (pinfunction "SW_26") (pintype "output"))
      (node (ref "L4") (pin "1") (pinfunction "1_1") (pintype "passive"))
      (node (ref "Q5") (pin "3") (pinfunction "S_3") (pintype "passive"))
      (node (ref "Q6") (pin "2") (pinfunction "D_2") (pintype "passive"))
    )
    (net (code "114") (name "Net-(IC12-TG)") (class "Default")
      (node (ref "IC12") (pin "25") (pinfunction "TG_25") (pintype "output"))
      (node (ref "R47") (pin "1") (pinfunction "1_1") (pintype "passive"))
    )
    (net (code "115") (name "Net-(IC12-VC)") (class "Default")
      (node (ref "C84") (pin "2") (pinfunction "2_2") (pintype "passive"))
      (node (ref "IC12") (pin "18") (pinfunction "VC_18") (pintype "passive"))
    )
    (net (code "116") (name "Net-(IC12-~{FAULT})") (class "Default")
      (node (ref "IC12") (pin "9") (pinfunction "~{FAULT}_9") (pintype "output"))
      (node (ref "R60") (pin "1") (pinfunction "1_1") (pintype "passive"))
    )
    (net (code "117") (name "Net-(L1A-1)") (class "Default")
      (node (ref "C1") (pin "2") (pinfunction "2_2") (pintype "passive"))
      (node (ref "L1") (pin "3") (pinfunction "1_3") (pintype "passive"))
      (node (ref "R1") (pin "2") (pinfunction "2_2") (pintype "passive"))
      (node (ref "X1") (pin "1") (pinfunction "1_1") (pintype "passive"))
    )
    (net (code "118") (name "Net-(L2-Pad2)") (class "Default")
      (node (ref "L2") (pin "2") (pinfunction "2_2") (pintype "passive"))
      (node (ref "R27") (pin "1") (pinfunction "1_1") (pintype "passive"))
    )
    (net (code "119") (name "Net-(L4-Pad2)") (class "Default")
      (node (ref "L4") (pin "2") (pinfunction "2_2") (pintype "passive"))
      (node (ref "R50") (pin "1") (pinfunction "1_1") (pintype "passive"))
    )
    (net (code "120") (name "Net-(LED1-AG)") (class "Default")
      (node (ref "LED1") (pin "GREEN") (pinfunction "AG_GREEN") (pintype "passive"))
      (node (ref "Q3") (pin "2") (pinfunction "S_2") (pintype "passive"))
    )
    (net (code "121") (name "Net-(LED1-C)") (class "Default")
      (node (ref "LED1") (pin "CC") (pinfunction "C_CC") (pintype "passive"))
      (node (ref "R42") (pin "1") (pinfunction "1_1") (pintype "passive"))
    )
    (net (code "122") (name "Net-(LED2-AG)") (class "Default")
      (node (ref "LED2") (pin "GREEN") (pinfunction "AG_GREEN") (pintype "passive"))
      (node (ref "Q7") (pin "2") (pinfunction "S_2") (pintype "passive"))
    )
    (net (code "123") (name "Net-(LED2-C)") (class "Default")
      (node (ref "LED2") (pin "CC") (pinfunction "C_CC") (pintype "passive"))
      (node (ref "R65") (pin "1") (pinfunction "1_1") (pintype "passive"))
    )
    (net (code "124") (name "Net-(Q1-G)") (class "Default")
      (node (ref "Q1") (pin "1") (pinfunction "G_1") (pintype "passive"))
      (node (ref "R24") (pin "2") (pinfunction "2_2") (pintype "passive"))
    )
    (net (code "125") (name "Net-(Q2-G)") (class "Default")
      (node (ref "Q2") (pin "1") (pinfunction "G_1") (pintype "passive"))
      (node (ref "R30") (pin "2") (pinfunction "2_2") (pintype "passive"))
    )
    (net (code "126") (name "Net-(Q3-D)") (class "Default")
      (node (ref "Q3") (pin "3") (pinfunction "D_3") (pintype "passive"))
      (node (ref "Q4") (pin "3") (pinfunction "D_3") (pintype "passive"))
    )
    (net (code "127") (name "Net-(Q5-G)") (class "Default")
      (node (ref "Q5") (pin "1") (pinfunction "G_1") (pintype "passive"))
      (node (ref "R47") (pin "2") (pinfunction "2_2") (pintype "passive"))
    )
    (net (code "128") (name "Net-(Q6-G)") (class "Default")
      (node (ref "Q6") (pin "1") (pinfunction "G_1") (pintype "passive"))
      (node (ref "R53") (pin "2") (pinfunction "2_2") (pintype "passive"))
    )
    (net (code "129") (name "Net-(Q7-D)") (class "Default")
      (node (ref "Q7") (pin "3") (pinfunction "D_3") (pintype "passive"))
      (node (ref "Q8") (pin "3") (pinfunction "D_3") (pintype "passive"))
    )
    (net (code "130") (name "Net-(R27-Pad1S)") (class "Default")
      (node (ref "R27") (pin "1S") (pinfunction "1S_1S") (pintype "passive"))
      (node (ref "R28") (pin "2") (pinfunction "2_2") (pintype "passive"))
    )
    (net (code "131") (name "Net-(R27-Pad2S)") (class "Default")
      (node (ref "R27") (pin "2S") (pinfunction "2S_2S") (pintype "passive"))
      (node (ref "R29") (pin "2") (pinfunction "2_2") (pintype "passive"))
    )
    (net (code "132") (name "Net-(R50-Pad1S)") (class "Default")
      (node (ref "R50") (pin "1S") (pinfunction "1S_1S") (pintype "passive"))
      (node (ref "R51") (pin "2") (pinfunction "2_2") (pintype "passive"))
    )
    (net (code "133") (name "Net-(R50-Pad2S)") (class "Default")
      (node (ref "R50") (pin "2S") (pinfunction "2S_2S") (pintype "passive"))
      (node (ref "R52") (pin "2") (pinfunction "2_2") (pintype "passive"))
    )
    (net (code "134") (name "Net-(X1B-1)") (class "Default")
      (node (ref "C1") (pin "1") (pinfunction "1_1") (pintype "passive"))
      (node (ref "L1") (pin "1") (pinfunction "1_1") (pintype "passive"))
      (node (ref "R1") (pin "1") (pinfunction "1_1") (pintype "passive"))
      (node (ref "X1") (pin "2") (pinfunction "1_2") (pintype "passive"))
    )
    (net (code "135") (name "Net-(X3A-S)") (class "Default")
      (node (ref "JP4") (pin "2") (pinfunction "2_2") (pintype "passive"))
      (node (ref "R15") (pin "2") (pinfunction "2_2") (pintype "passive"))
      (node (ref "X3") (pin "1") (pinfunction "S_1") (pintype "passive"))
    )
    (net (code "136") (name "OE#1") (class "Default")
      (node (ref "IC10") (pin "4") (pinfunction "EV/UVLO_4") (pintype "input"))
      (node (ref "OE#2") (pin "2") (pinfunction "2_2") (pintype "passive"))
      (node (ref "OE1") (pin "1") (pinfunction "P$1_1") (pintype "bidirectional"))
      (node (ref "Q3") (pin "1") (pinfunction "G_1") (pintype "passive"))
    )
    (net (code "137") (name "OE#2") (class "Default")
      (node (ref "IC12") (pin "4") (pinfunction "EV/UVLO_4") (pintype "input"))
      (node (ref "OE#1") (pin "2") (pinfunction "2_2") (pintype "passive"))
      (node (ref "Q7") (pin "1") (pinfunction "G_1") (pintype "passive"))
    )
    (net (code "138") (name "OE_SYNC") (class "Default")
      (node (ref "IC8") (pin "36") (pinfunction "PF7_36") (pintype "bidirectional"))
      (node (ref "RN1") (pin "8") (pinfunction "2_8") (pintype "passive"))
    )
    (net (code "139") (name "PE") (class "Default")
      (node (ref "C2") (pin "2") (pinfunction "2_2") (pintype "passive"))
      (node (ref "C3") (pin "1") (pinfunction "1_1") (pintype "passive"))
      (node (ref "C50") (pin "1") (pinfunction "1_1") (pintype "passive"))
      (node (ref "C57") (pin "1") (pinfunction "1_1") (pintype "passive"))
      (node (ref "C73") (pin "1") (pinfunction "1_1") (pintype "passive"))
      (node (ref "C80") (pin "1") (pinfunction "1_1") (pintype "passive"))
      (node (ref "J1") (pin "1") (pinfunction "P$1_1") (pintype "bidirectional"))
      (node (ref "J1") (pin "2") (pinfunction "P$1_2") (pintype "bidirectional"))
    )
    (net (code "140") (name "PWRGOOD") (class "Default")
      (node (ref "IC2") (pin "6") (pinfunction "PWRGD_6") (pintype "output"))
      (node (ref "IC8") (pin "40") (pinfunction "PB4_40") (pintype "bidirectional"))
    )
    (net (code "141") (name "REF_12") (class "Default")
      (node (ref "IC7") (pin "1") (pinfunction "REF_1") (pintype "bidirectional"))
      (node (ref "JP5") (pin "2") (pinfunction "2_2") (pintype "passive"))
    )
    (net (code "142") (name "SCLK") (class "Default")
      (node (ref "IC8") (pin "29") (pinfunction "PA8_29") (pintype "bidirectional"))
      (node (ref "RN1") (pin "7") (pinfunction "2_7") (pintype "passive"))
    )
    (net (code "143") (name "SWCLK") (class "Default")
      (node (ref "IC8") (pin "37") (pinfunction "PA14_37") (pintype "bidirectional"))
      (node (ref "RN2") (pin "2") (pinfunction "1_2") (pintype "passive"))
    )
    (net (code "144") (name "SWDIO") (class "Default")
      (node (ref "IC8") (pin "34") (pinfunction "PA13_34") (pintype "bidirectional"))
      (node (ref "RN2") (pin "3") (pinfunction "1_3") (pintype "passive"))
    )
    (net (code "145") (name "SWO") (class "Default")
      (node (ref "IC8") (pin "39") (pinfunction "PB3_39") (pintype "bidirectional"))
      (node (ref "RN2") (pin "1") (pinfunction "1_1") (pintype "passive"))
    )
    (net (code "146") (name "TCK") (class "Default")
      (node (ref "IC6") (pin "5") (pinfunction "IO4_5") (pintype "bidirectional"))
      (node (ref "RN2") (pin "7") (pinfunction "2_7") (pintype "passive"))
      (node (ref "X3") (pin "2") (pinfunction "S_2") (pintype "passive"))
    )
    (net (code "147") (name "TEMP#1") (class "Default")
      (node (ref "C33") (pin "2") (pinfunction "2_2") (pintype "passive"))
      (node (ref "IC8") (pin "10") (pinfunction "PA0_10") (pintype "bidirectional"))
      (node (ref "NTC1") (pin "2") (pinfunction "P$2_2") (pintype "bidirectional"))
      (node (ref "R16") (pin "1") (pinfunction "1_1") (pintype "passive"))
    )
    (net (code "148") (name "TEMP#2") (class "Default")
      (node (ref "C34") (pin "2") (pinfunction "2_2") (pintype "passive"))
      (node (ref "IC8") (pin "16") (pinfunction "PA6_16") (pintype "bidirectional"))
      (node (ref "NTC2") (pin "2") (pinfunction "P$2_2") (pintype "bidirectional"))
      (node (ref "R17") (pin "1") (pinfunction "1_1") (pintype "passive"))
    )
    (net (code "149") (name "TMS") (class "Default")
      (node (ref "IC6") (pin "4") (pinfunction "IO3_4") (pintype "bidirectional"))
      (node (ref "RN2") (pin "6") (pinfunction "2_6") (pintype "passive"))
      (node (ref "X3") (pin "4") (pinfunction "S_4") (pintype "passive"))
    )
    (net (code "150") (name "UART_RX") (class "Default")
      (node (ref "IC3") (pin "12") (pinfunction "B3_12") (pintype "output"))
      (node (ref "IC8") (pin "13") (pinfunction "PA3_13") (pintype "bidirectional"))
    )
    (net (code "151") (name "UART_TX") (class "Default")
      (node (ref "IC3") (pin "11") (pinfunction "B4_11") (pintype "input"))
      (node (ref "IC8") (pin "12") (pinfunction "PA2_12") (pintype "bidirectional"))
    )
    (net (code "152") (name "U_MON#1") (class "Default")
      (node (ref "C38") (pin "2") (pinfunction "2_2") (pintype "passive"))
      (node (ref "IC8") (pin "18") (pinfunction "PB0_18") (pintype "bidirectional"))
      (node (ref "R18") (pin "1") (pinfunction "1_1") (pintype "passive"))
    )
    (net (code "153") (name "U_MON#2") (class "Default")
      (node (ref "C40") (pin "2") (pinfunction "2_2") (pintype "passive"))
      (node (ref "IC8") (pin "20") (pinfunction "PB2_20") (pintype "bidirectional"))
      (node (ref "R20") (pin "1") (pinfunction "1_1") (pintype "passive"))
    )
    (net (code "154") (name "U_MON1") (class "Default")
      (node (ref "R18") (pin "2") (pinfunction "2_2") (pintype "passive"))
      (node (ref "R34") (pin "1") (pinfunction "1_1") (pintype "passive"))
      (node (ref "R40") (pin "2") (pinfunction "2_2") (pintype "passive"))
    )
    (net (code "155") (name "U_MON2") (class "Default")
      (node (ref "R20") (pin "2") (pinfunction "2_2") (pintype "passive"))
      (node (ref "R57") (pin "1") (pinfunction "1_1") (pintype "passive"))
      (node (ref "R63") (pin "2") (pinfunction "2_2") (pintype "passive"))
    )
    (net (code "156") (name "U_SET#1") (class "Default")
      (node (ref "R41") (pin "1") (pinfunction "1_1") (pintype "passive"))
      (node (ref "USET1") (pin "1") (pinfunction "P$1_1") (pintype "bidirectional"))
      (node (ref "U_SET1") (pin "1") (pinfunction "1_1") (pintype "passive"))
    )
    (net (code "157") (name "U_SET#2") (class "Default")
      (node (ref "R64") (pin "1") (pinfunction "1_1") (pintype "passive"))
      (node (ref "U_SET2") (pin "1") (pinfunction "1_1") (pintype "passive"))
    )
    (net (code "158") (name "V+") (class "Default")
      (node (ref "C17") (pin "1") (pinfunction "1_1") (pintype "passive"))
      (node (ref "C20") (pin "2") (pinfunction "2_2") (pintype "passive"))
      (node (ref "C7") (pin "1") (pinfunction "1_1") (pintype "passive"))
      (node (ref "IC1") (pin "1") (pinfunction "VDD1_1") (pintype "passive"))
      (node (ref "IC3") (pin "1") (pinfunction "VDD1_1") (pintype "passive"))
      (node (ref "IC3") (pin "7") (pinfunction "EN1_7") (pintype "input"))
      (node (ref "IC4") (pin "8") (pinfunction "VCC_8") (pintype "power_in"))
      (node (ref "R11") (pin "1") (pinfunction "1_1") (pintype "passive"))
      (node (ref "R12") (pin "1") (pinfunction "1_1") (pintype "passive"))
      (node (ref "R13") (pin "1") (pinfunction "1_1") (pintype "passive"))
      (node (ref "X2") (pin "1") (pinfunction "1_1") (pintype "passive"))
    )
    (net (code "159") (name "VDDA") (class "Default")
      (node (ref "C32") (pin "2") (pinfunction "2_2") (pintype "passive"))
      (node (ref "C35") (pin "2") (pinfunction "2_2") (pintype "passive"))
      (node (ref "FB1") (pin "P$2") (pinfunction "2_P$2") (pintype "passive"))
      (node (ref "IC8") (pin "24") (pinfunction "VDDSD_24") (pintype "passive"))
      (node (ref "IC8") (pin "9") (pinfunction "VDDA/VREF+_9") (pintype "passive"))
    )
    (net (code "160") (name "VOUT1+") (class "Default")
      (node (ref "C53") (pin "1") (pinfunction "1_1") (pintype "passive"))
      (node (ref "C54") (pin "1") (pinfunction "1_1") (pintype "passive"))
      (node (ref "C56") (pin "+") (pinfunction "+_+") (pintype "passive"))
      (node (ref "L3") (pin "1") (pinfunction "1_1") (pintype "passive"))
      (node (ref "R27") (pin "2") (pinfunction "2_2") (pintype "passive"))
      (node (ref "R33") (pin "2") (pinfunction "2_2") (pintype "passive"))
      (node (ref "R34") (pin "2") (pinfunction "2_2") (pintype "passive"))
    )
    (net (code "161") (name "VOUT2+") (class "Default")
      (node (ref "C76") (pin "1") (pinfunction "1_1") (pintype "passive"))
      (node (ref "C77") (pin "1") (pinfunction "1_1") (pintype "passive"))
      (node (ref "C79") (pin "+") (pinfunction "+_+") (pintype "passive"))
      (node (ref "L5") (pin "1") (pinfunction "1_1") (pintype "passive"))
      (node (ref "R50") (pin "2") (pinfunction "2_2") (pintype "passive"))
      (node (ref "R56") (pin "2") (pinfunction "2_2") (pintype "passive"))
      (node (ref "R57") (pin "2") (pinfunction "2_2") (pintype "passive"))
    )
    (net (code "162") (name "VOUT_LC1+") (class "Default")
      (node (ref "C50") (pin "2") (pinfunction "2_2") (pintype "passive"))
      (node (ref "C51") (pin "1") (pinfunction "1_1") (pintype "passive"))
      (node (ref "C55") (pin "+") (pinfunction "+_+") (pintype "passive"))
      (node (ref "CH1") (pin "TIP") (pinfunction "TIP_TIP") (pintype "bidirectional"))
      (node (ref "J2") (pin "1") (pinfunction "1_1") (pintype "passive"))
      (node (ref "J2") (pin "1.1") (pinfunction "1_1.1") (pintype "passive"))
      (node (ref "L3") (pin "2") (pinfunction "2_2") (pintype "passive"))
      (node (ref "ZD2") (pin "C") (pinfunction "C_C") (pintype "passive"))
    )
    (net (code "163") (name "VOUT_LC2+") (class "Default")
      (node (ref "C73") (pin "2") (pinfunction "2_2") (pintype "passive"))
      (node (ref "C74") (pin "1") (pinfunction "1_1") (pintype "passive"))
      (node (ref "C78") (pin "+") (pinfunction "+_+") (pintype "passive"))
      (node (ref "CH2") (pin "TIP") (pinfunction "TIP_TIP") (pintype "bidirectional"))
      (node (ref "J4") (pin "1") (pinfunction "1_1") (pintype "passive"))
      (node (ref "J4") (pin "1.1") (pinfunction "1_1.1") (pintype "passive"))
      (node (ref "L5") (pin "2") (pinfunction "2_2") (pintype "passive"))
      (node (ref "ZD3") (pin "C") (pinfunction "C_C") (pintype "passive"))
    )
    (net (code "164") (name "VREF1") (class "Default")
      (node (ref "C47") (pin "1") (pinfunction "1_1") (pintype "passive"))
      (node (ref "IC10") (pin "10") (pinfunction "FBIN_10") (pintype "input"))
      (node (ref "IC10") (pin "13") (pinfunction "CTRL2_13") (pintype "input"))
      (node (ref "IC10") (pin "5") (pinfunction "VREF_5") (pintype "output"))
      (node (ref "R43") (pin "2") (pinfunction "2_2") (pintype "passive"))
    )
    (net (code "165") (name "VREF2") (class "Default")
      (node (ref "C70") (pin "1") (pinfunction "1_1") (pintype "passive"))
      (node (ref "IC12") (pin "10") (pinfunction "FBIN_10") (pintype "input"))
      (node (ref "IC12") (pin "13") (pinfunction "CTRL2_13") (pintype "input"))
      (node (ref "IC12") (pin "5") (pinfunction "VREF_5") (pintype "output"))
      (node (ref "R66") (pin "2") (pinfunction "2_2") (pintype "passive"))
    )
    (net (code "166") (name "unconnected-(IC7-~{RDY}-Pad8)") (class "Default")
      (node (ref "IC7") (pin "8") (pinfunction "~{RDY}_8") (pintype "output"))
    )
    (net (code "167") (name "unconnected-(IC8-PA15-Pad38)") (class "Default")
      (node (ref "IC8") (pin "38") (pinfunction "PA15_38") (pintype "bidirectional"))
    )
    (net (code "168") (name "unconnected-(IC8-PB7-Pad43)") (class "Default")
      (node (ref "IC8") (pin "43") (pinfunction "PB7_43") (pintype "bidirectional"))
    )
    (net (code "169") (name "unconnected-(IC8-PB8-Pad45)") (class "Default")
      (node (ref "IC8") (pin "45") (pinfunction "PB8_45") (pintype "bidirectional"))
    )
    (net (code "170") (name "unconnected-(IC8-PB9-Pad46)") (class "Default")
      (node (ref "IC8") (pin "46") (pinfunction "PB9_46") (pintype "bidirectional"))
    )
    (net (code "171") (name "unconnected-(IC8-PB14-Pad26)") (class "Default")
      (node (ref "IC8") (pin "26") (pinfunction "PB14_26") (pintype "bidirectional"))
    )
    (net (code "172") (name "unconnected-(IC8-PB15-Pad27)") (class "Default")
      (node (ref "IC8") (pin "27") (pinfunction "PB15_27") (pintype "bidirectional"))
    )
    (net (code "173") (name "unconnected-(IC8-PD8-Pad28)") (class "Default")
      (node (ref "IC8") (pin "28") (pinfunction "PD8_28") (pintype "bidirectional"))
    )
    (net (code "174") (name "unconnected-(IC8-PE9-Pad22)") (class "Default")
      (node (ref "IC8") (pin "22") (pinfunction "PE9_22") (pintype "bidirectional"))
    )
    (net (code "175") (name "unconnected-(IC8-VBAT-Pad1)") (class "Default")
      (node (ref "IC8") (pin "1") (pinfunction "VBAT_1") (pintype "passive"))
    )
    (net (code "176") (name "unconnected-(IC10-IVINMON-Pad8)") (class "Default")
      (node (ref "IC10") (pin "8") (pinfunction "IVINMON_8") (pintype "output"))
    )
    (net (code "177") (name "unconnected-(IC10-PWMOUT-Pad24)") (class "Default")
      (node (ref "IC10") (pin "24") (pinfunction "PWMOUT_24") (pintype "output"))
    )
    (net (code "178") (name "unconnected-(IC12-IVINMON-Pad8)") (class "Default")
      (node (ref "IC12") (pin "8") (pinfunction "IVINMON_8") (pintype "output"))
    )
    (net (code "179") (name "unconnected-(IC12-PWMOUT-Pad24)") (class "Default")
      (node (ref "IC12") (pin "24") (pinfunction "PWMOUT_24") (pintype "output"))
    )
    (net (code "180") (name "~{DAC_CLR}") (class "Default")
      (node (ref "IC7") (pin "12") (pinfunction "~{CLR}_12") (pintype "input"))
      (node (ref "JP3") (pin "1") (pinfunction "1_1") (pintype "passive"))
    )
    (net (code "181") (name "~{LDAC}") (class "Default")
      (node (ref "IC7") (pin "14") (pinfunction "~{LDAC}_14") (pintype "input"))
      (node (ref "JP2") (pin "1") (pinfunction "1_1") (pintype "passive"))
    )
    (net (code "182") (name "~{RESET}") (class "Default")
      (node (ref "IC1") (pin "15") (pinfunction "B1_15") (pintype "output"))
      (node (ref "IC8") (pin "7") (pinfunction "NRST_7") (pintype "input"))
      (node (ref "JP3") (pin "2") (pinfunction "2_2") (pintype "passive"))
      (node (ref "RN2") (pin "4") (pinfunction "1_4") (pintype "passive"))
    )
  )
)
